# BackBoard.net
KiCad netlist of a schematic drawn in Altium Designer
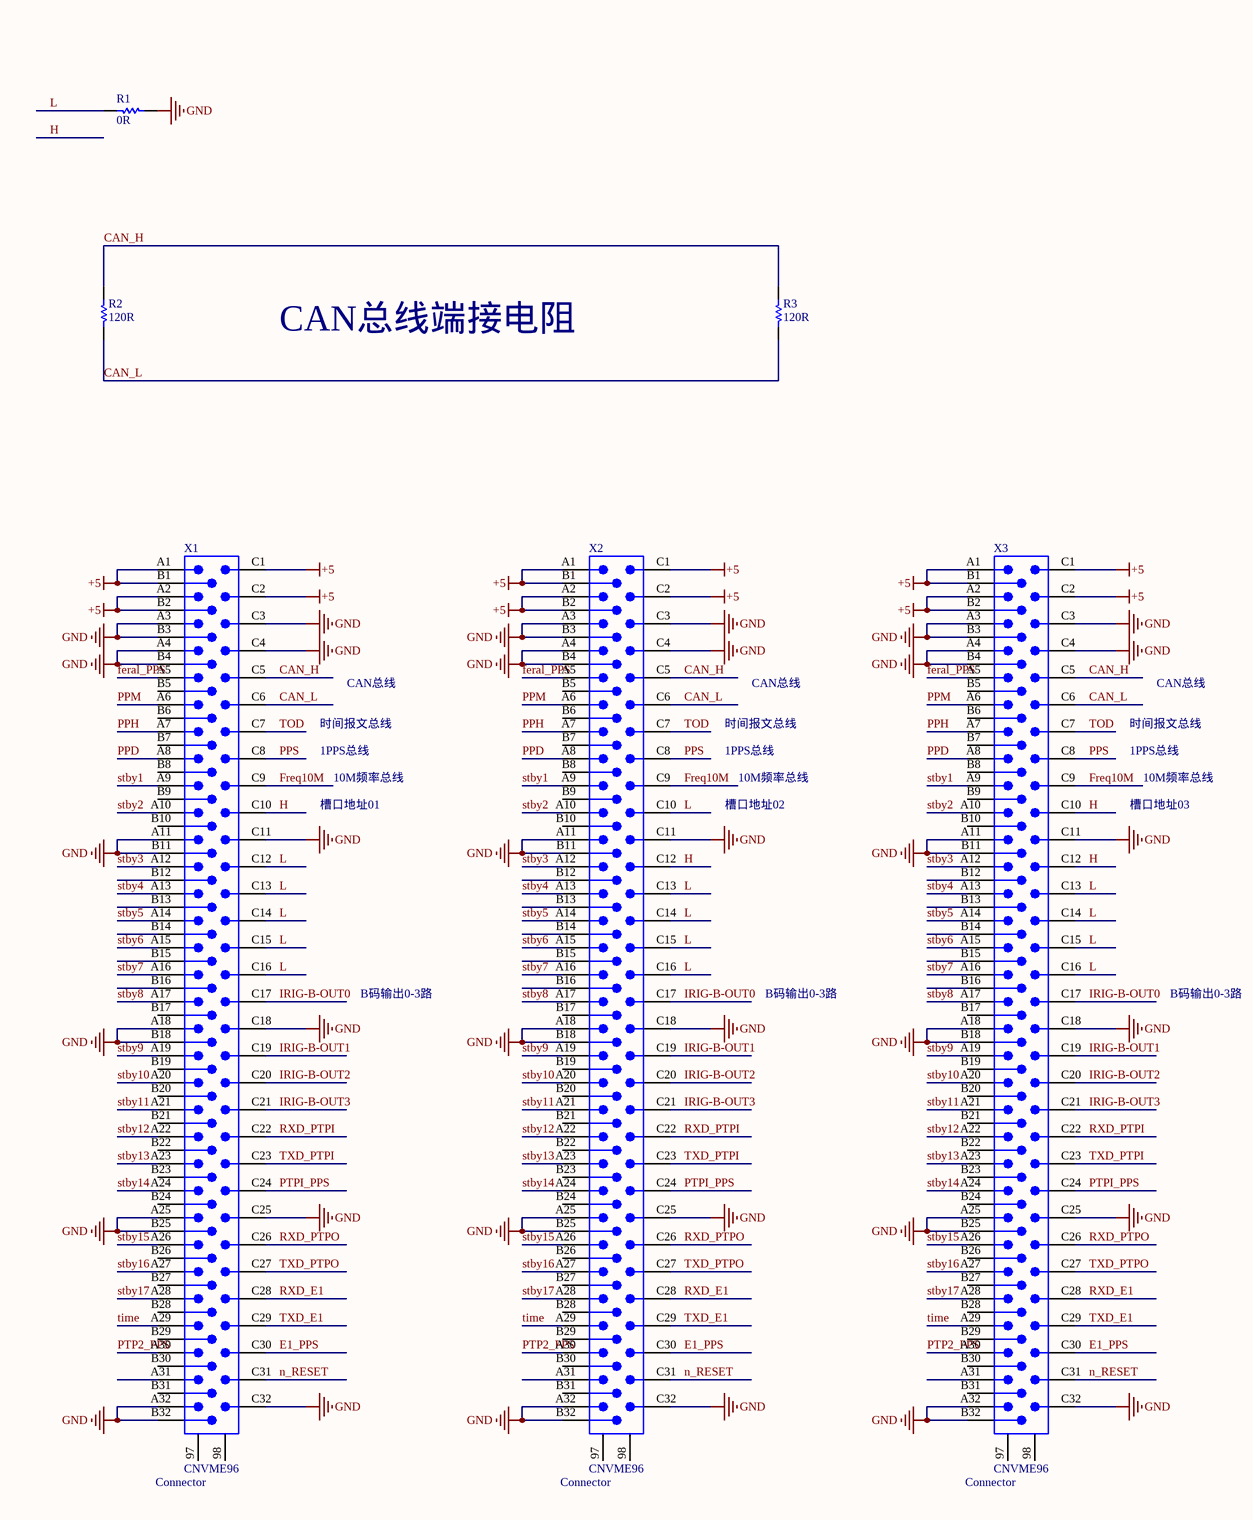
[diagram p0: BackBoard.SchDoc, top left]
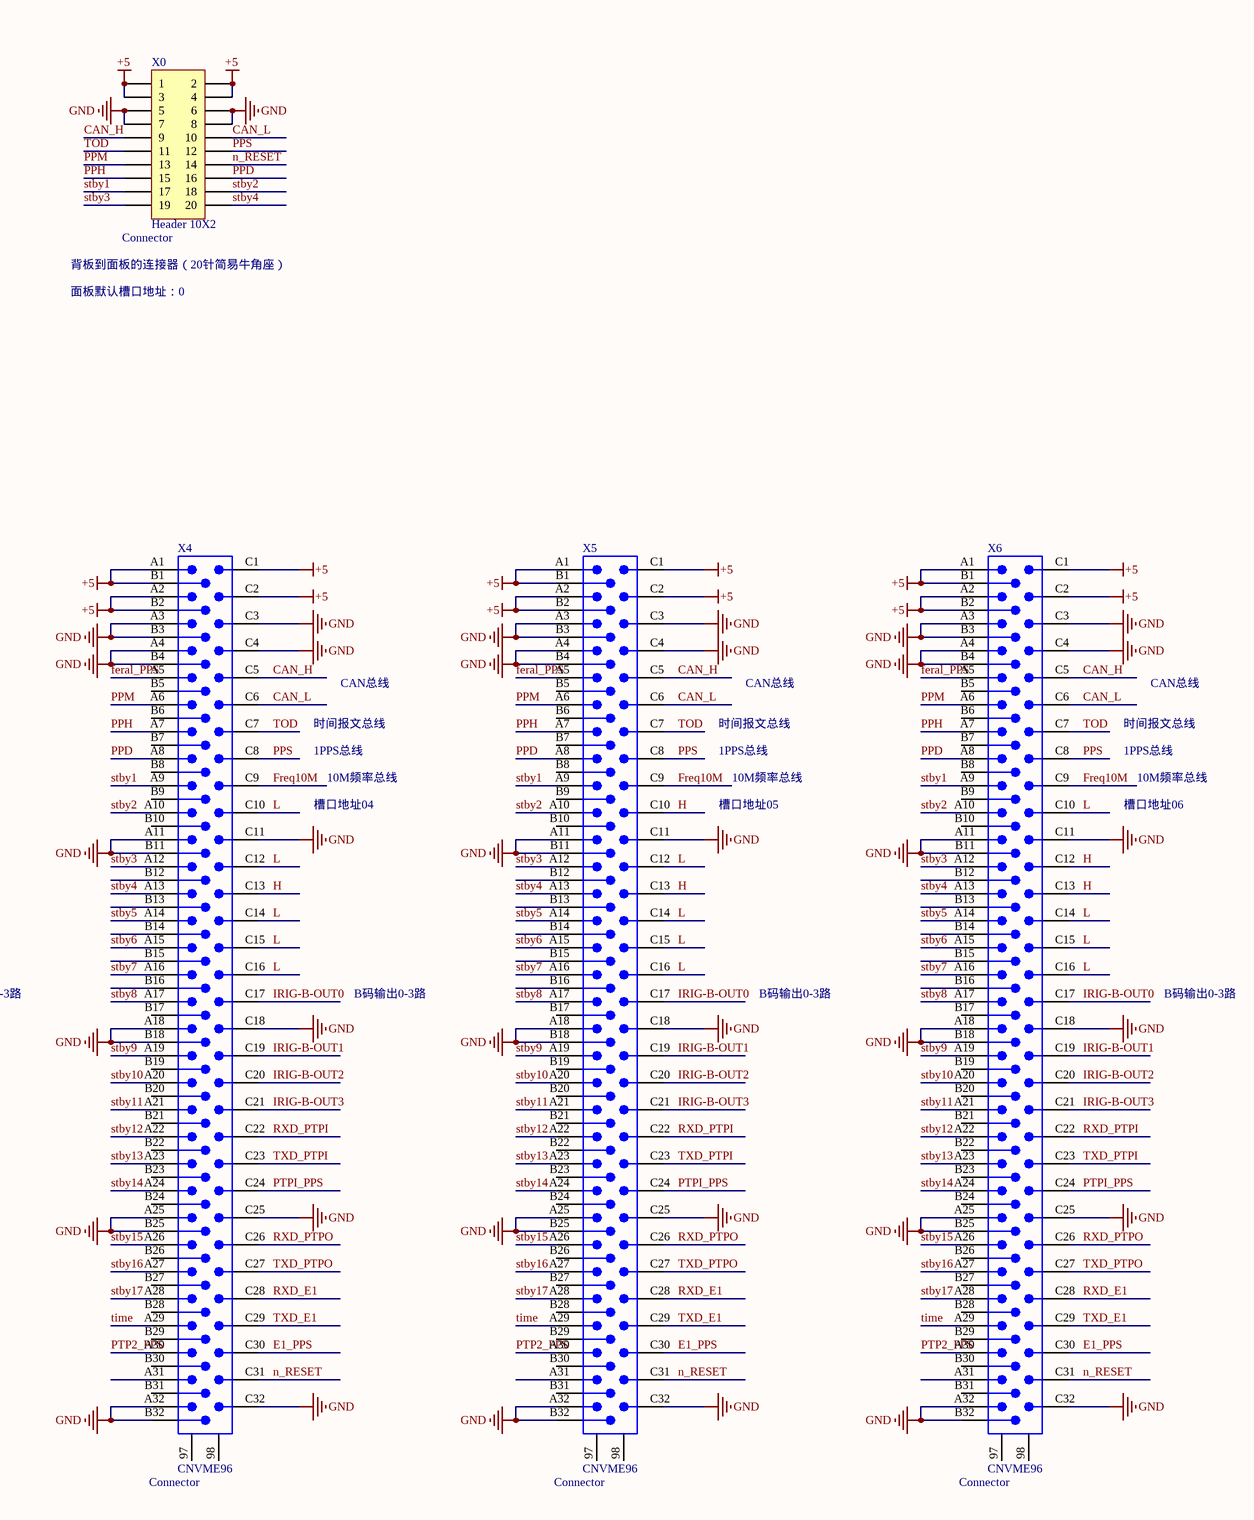
[diagram p1: BackBoard.SchDoc, top right]
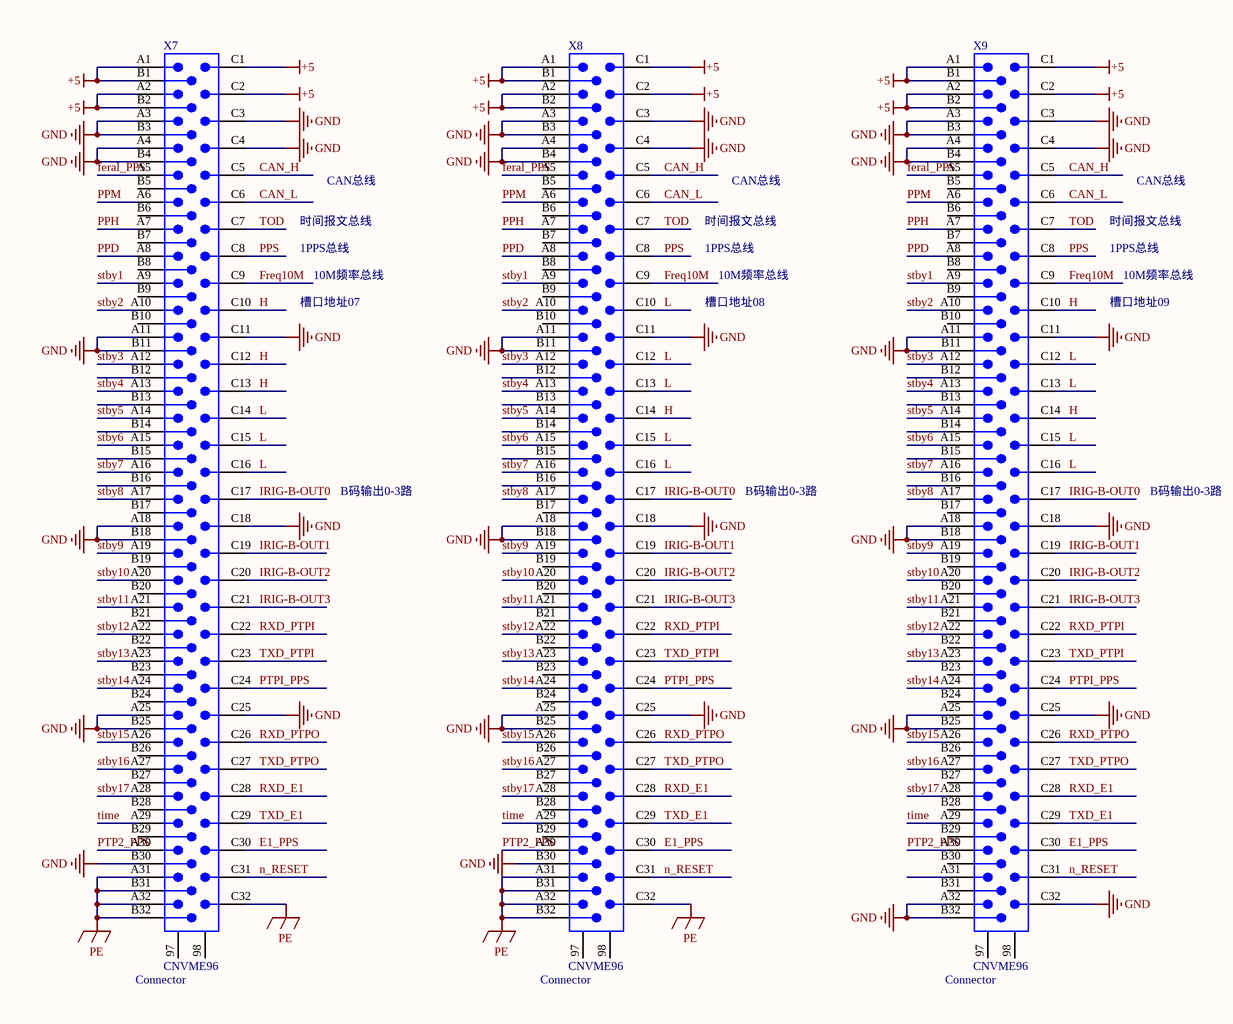
[diagram p2: BackBoard.SchDoc, bottom left]
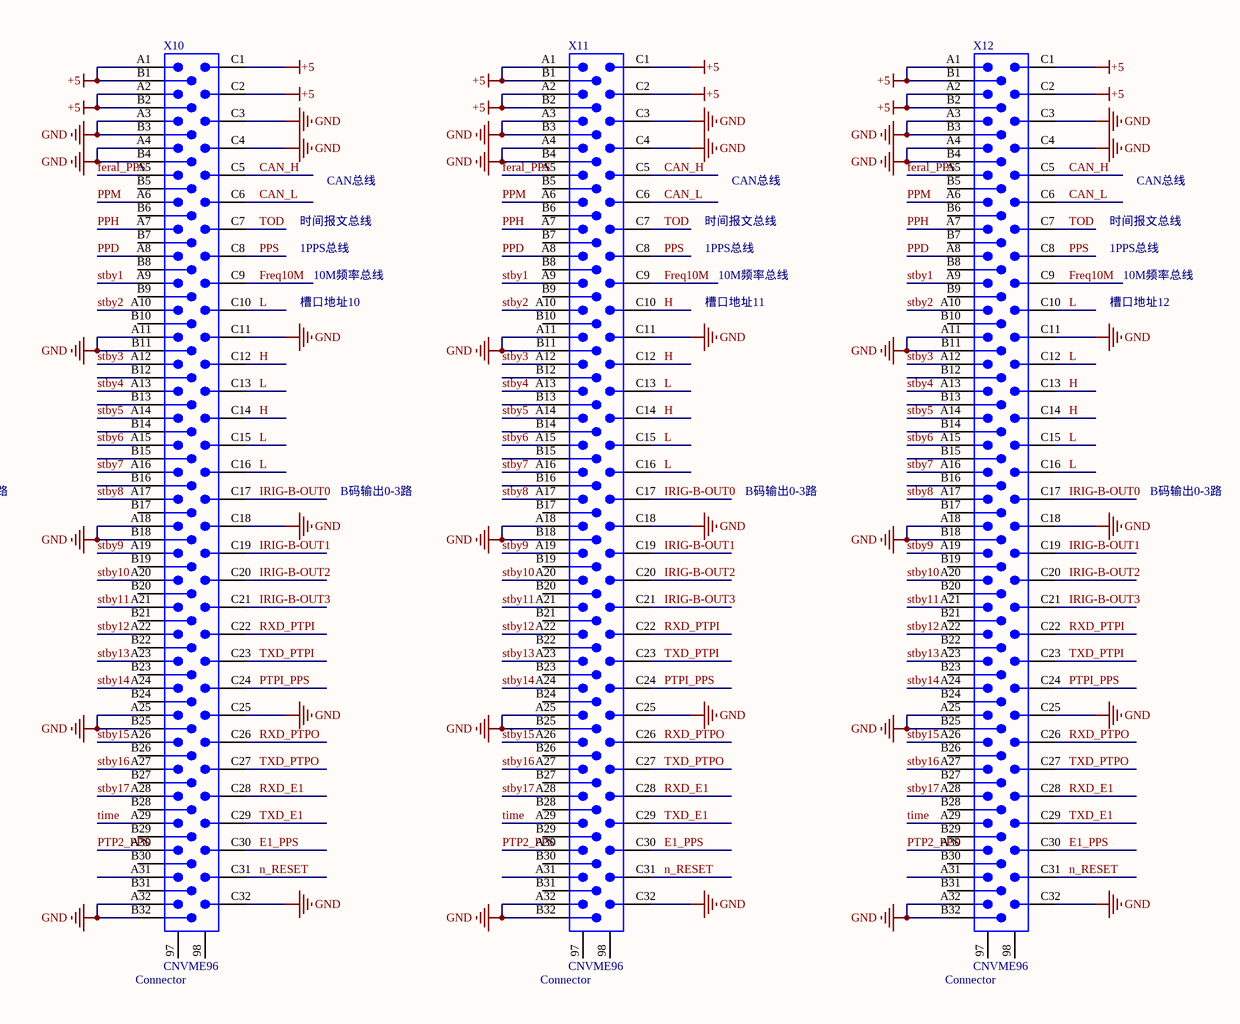
[diagram p3: BackBoard.SchDoc, bottom right]

(export (version "E")
  (design (tool "Eeschema 10.0.6"))
  (components
    (comp (ref "R1")
      (value "0R")
      (footprint "0603_XF")
      (description "Resistor")
      (fields (field (name "Comment") "Res1") (field (name "PUBLISHER") "Altium Limited"))
      (libsource (lib "Miscellaneous Devices") (part "Res1"))
    )
    (comp (ref "R2")
      (value "120R")
      (footprint "0603_XF")
      (description "Resistor")
      (fields (field (name "Comment") "Res1") (field (name "PUBLISHER") "Altium Limited"))
      (libsource (lib "Miscellaneous Devices") (part "Res1"))
    )
    (comp (ref "R3")
      (value "120R")
      (footprint "0603_XF")
      (description "Resistor")
      (fields (field (name "Comment") "Res1") (field (name "PUBLISHER") "Altium Limited"))
      (libsource (lib "Miscellaneous Devices") (part "Res1"))
    )
    (comp (ref "X0")
      (value "Header 10X2")
      (footprint "HDR2X10")
      (description "Header, 10-Pin, Dual row")
      (fields (field (name "SYSTEM") "Connector") (field (name "PUBLISHER") "Altium Limited"))
      (libsource (lib "Miscellaneous Connectors") (part "Header 10X2"))
    )
    (comp (ref "X1")
      (value "CNVME96")
      (footprint "CONNECT_96_Female")
      (description "96-Pin Connector (3x32 2.54mm grid)")
      (fields (field (name "SYSTEM") "Connector"))
      (libsource (lib "BTS4000") (part "CNVME96"))
    )
    (comp (ref "X2")
      (value "CNVME96")
      (footprint "CONNECT_96_Female")
      (description "96-Pin Connector (3x32 2.54mm grid)")
      (fields (field (name "SYSTEM") "Connector"))
      (libsource (lib "BTS4000") (part "CNVME96"))
    )
    (comp (ref "X3")
      (value "CNVME96")
      (footprint "CONNECT_96_Female")
      (description "96-Pin Connector (3x32 2.54mm grid)")
      (fields (field (name "SYSTEM") "Connector"))
      (libsource (lib "BTS4000") (part "CNVME96"))
    )
    (comp (ref "X4")
      (value "CNVME96")
      (footprint "CONNECT_96_Female")
      (description "96-Pin Connector (3x32 2.54mm grid)")
      (fields (field (name "SYSTEM") "Connector"))
      (libsource (lib "BTS4000") (part "CNVME96"))
    )
    (comp (ref "X5")
      (value "CNVME96")
      (footprint "CONNECT_96_Female")
      (description "96-Pin Connector (3x32 2.54mm grid)")
      (fields (field (name "SYSTEM") "Connector"))
      (libsource (lib "BTS4000") (part "CNVME96"))
    )
    (comp (ref "X6")
      (value "CNVME96")
      (footprint "CONNECT_96_Female")
      (description "96-Pin Connector (3x32 2.54mm grid)")
      (fields (field (name "SYSTEM") "Connector"))
      (libsource (lib "BTS4000") (part "CNVME96"))
    )
    (comp (ref "X7")
      (value "CNVME96")
      (footprint "CONNECT_96_Female")
      (description "96-Pin Connector (3x32 2.54mm grid)")
      (fields (field (name "SYSTEM") "Connector"))
      (libsource (lib "BTS4000") (part "CNVME96"))
    )
    (comp (ref "X8")
      (value "CNVME96")
      (footprint "CONNECT_96_Female")
      (description "96-Pin Connector (3x32 2.54mm grid)")
      (fields (field (name "SYSTEM") "Connector"))
      (libsource (lib "BTS4000") (part "CNVME96"))
    )
    (comp (ref "X9")
      (value "CNVME96")
      (footprint "CONNECT_96_Female")
      (description "96-Pin Connector (3x32 2.54mm grid)")
      (fields (field (name "SYSTEM") "Connector"))
      (libsource (lib "BTS4000") (part "CNVME96"))
    )
    (comp (ref "X10")
      (value "CNVME96")
      (footprint "CONNECT_96_Female")
      (description "96-Pin Connector (3x32 2.54mm grid)")
      (fields (field (name "SYSTEM") "Connector"))
      (libsource (lib "BTS4000") (part "CNVME96"))
    )
    (comp (ref "X11")
      (value "CNVME96")
      (footprint "CONNECT_96_Female")
      (description "96-Pin Connector (3x32 2.54mm grid)")
      (fields (field (name "SYSTEM") "Connector"))
      (libsource (lib "BTS4000") (part "CNVME96"))
    )
    (comp (ref "X12")
      (value "CNVME96")
      (footprint "CONNECT_96_Female")
      (description "96-Pin Connector (3x32 2.54mm grid)")
      (fields (field (name "SYSTEM") "Connector"))
      (libsource (lib "BTS4000") (part "CNVME96"))
    )
  )
  (nets
    (net (code "1") (name "+5") (class "Default")
      (node (ref "X0") (pin "1") (pinfunction "1_1") (pintype "passive"))
      (node (ref "X0") (pin "2") (pinfunction "2_2") (pintype "passive"))
      (node (ref "X0") (pin "3") (pinfunction "3_3") (pintype "passive"))
      (node (ref "X0") (pin "4") (pinfunction "4_4") (pintype "passive"))
      (node (ref "X1") (pin "A1") (pinfunction "A1_A1") (pintype "passive"))
      (node (ref "X1") (pin "A2") (pinfunction "A2_A2") (pintype "passive"))
      (node (ref "X1") (pin "B1") (pinfunction "B1_B1") (pintype "passive"))
      (node (ref "X1") (pin "B2") (pinfunction "B2_B2") (pintype "passive"))
      (node (ref "X1") (pin "C1") (pinfunction "C1_C1") (pintype "passive"))
      (node (ref "X1") (pin "C2") (pinfunction "C2_C2") (pintype "passive"))
      (node (ref "X10") (pin "A1") (pinfunction "A1_A1") (pintype "passive"))
      (node (ref "X10") (pin "A2") (pinfunction "A2_A2") (pintype "passive"))
      (node (ref "X10") (pin "B1") (pinfunction "B1_B1") (pintype "passive"))
      (node (ref "X10") (pin "B2") (pinfunction "B2_B2") (pintype "passive"))
      (node (ref "X10") (pin "C1") (pinfunction "C1_C1") (pintype "passive"))
      (node (ref "X10") (pin "C2") (pinfunction "C2_C2") (pintype "passive"))
      (node (ref "X11") (pin "A1") (pinfunction "A1_A1") (pintype "passive"))
      (node (ref "X11") (pin "A2") (pinfunction "A2_A2") (pintype "passive"))
      (node (ref "X11") (pin "B1") (pinfunction "B1_B1") (pintype "passive"))
      (node (ref "X11") (pin "B2") (pinfunction "B2_B2") (pintype "passive"))
      (node (ref "X11") (pin "C1") (pinfunction "C1_C1") (pintype "passive"))
      (node (ref "X11") (pin "C2") (pinfunction "C2_C2") (pintype "passive"))
      (node (ref "X12") (pin "A1") (pinfunction "A1_A1") (pintype "passive"))
      (node (ref "X12") (pin "A2") (pinfunction "A2_A2") (pintype "passive"))
      (node (ref "X12") (pin "B1") (pinfunction "B1_B1") (pintype "passive"))
      (node (ref "X12") (pin "B2") (pinfunction "B2_B2") (pintype "passive"))
      (node (ref "X12") (pin "C1") (pinfunction "C1_C1") (pintype "passive"))
      (node (ref "X12") (pin "C2") (pinfunction "C2_C2") (pintype "passive"))
      (node (ref "X2") (pin "A1") (pinfunction "A1_A1") (pintype "passive"))
      (node (ref "X2") (pin "A2") (pinfunction "A2_A2") (pintype "passive"))
      (node (ref "X2") (pin "B1") (pinfunction "B1_B1") (pintype "passive"))
      (node (ref "X2") (pin "B2") (pinfunction "B2_B2") (pintype "passive"))
      (node (ref "X2") (pin "C1") (pinfunction "C1_C1") (pintype "passive"))
      (node (ref "X2") (pin "C2") (pinfunction "C2_C2") (pintype "passive"))
      (node (ref "X3") (pin "A1") (pinfunction "A1_A1") (pintype "passive"))
      (node (ref "X3") (pin "A2") (pinfunction "A2_A2") (pintype "passive"))
      (node (ref "X3") (pin "B1") (pinfunction "B1_B1") (pintype "passive"))
      (node (ref "X3") (pin "B2") (pinfunction "B2_B2") (pintype "passive"))
      (node (ref "X3") (pin "C1") (pinfunction "C1_C1") (pintype "passive"))
      (node (ref "X3") (pin "C2") (pinfunction "C2_C2") (pintype "passive"))
      (node (ref "X4") (pin "A1") (pinfunction "A1_A1") (pintype "passive"))
      (node (ref "X4") (pin "A2") (pinfunction "A2_A2") (pintype "passive"))
      (node (ref "X4") (pin "B1") (pinfunction "B1_B1") (pintype "passive"))
      (node (ref "X4") (pin "B2") (pinfunction "B2_B2") (pintype "passive"))
      (node (ref "X4") (pin "C1") (pinfunction "C1_C1") (pintype "passive"))
      (node (ref "X4") (pin "C2") (pinfunction "C2_C2") (pintype "passive"))
      (node (ref "X5") (pin "A1") (pinfunction "A1_A1") (pintype "passive"))
      (node (ref "X5") (pin "A2") (pinfunction "A2_A2") (pintype "passive"))
      (node (ref "X5") (pin "B1") (pinfunction "B1_B1") (pintype "passive"))
      (node (ref "X5") (pin "B2") (pinfunction "B2_B2") (pintype "passive"))
      (node (ref "X5") (pin "C1") (pinfunction "C1_C1") (pintype "passive"))
      (node (ref "X5") (pin "C2") (pinfunction "C2_C2") (pintype "passive"))
      (node (ref "X6") (pin "A1") (pinfunction "A1_A1") (pintype "passive"))
      (node (ref "X6") (pin "A2") (pinfunction "A2_A2") (pintype "passive"))
      (node (ref "X6") (pin "B1") (pinfunction "B1_B1") (pintype "passive"))
      (node (ref "X6") (pin "B2") (pinfunction "B2_B2") (pintype "passive"))
      (node (ref "X6") (pin "C1") (pinfunction "C1_C1") (pintype "passive"))
      (node (ref "X6") (pin "C2") (pinfunction "C2_C2") (pintype "passive"))
      (node (ref "X7") (pin "A1") (pinfunction "A1_A1") (pintype "passive"))
      (node (ref "X7") (pin "A2") (pinfunction "A2_A2") (pintype "passive"))
      (node (ref "X7") (pin "B1") (pinfunction "B1_B1") (pintype "passive"))
      (node (ref "X7") (pin "B2") (pinfunction "B2_B2") (pintype "passive"))
      (node (ref "X7") (pin "C1") (pinfunction "C1_C1") (pintype "passive"))
      (node (ref "X7") (pin "C2") (pinfunction "C2_C2") (pintype "passive"))
      (node (ref "X8") (pin "A1") (pinfunction "A1_A1") (pintype "passive"))
      (node (ref "X8") (pin "A2") (pinfunction "A2_A2") (pintype "passive"))
      (node (ref "X8") (pin "B1") (pinfunction "B1_B1") (pintype "passive"))
      (node (ref "X8") (pin "B2") (pinfunction "B2_B2") (pintype "passive"))
      (node (ref "X8") (pin "C1") (pinfunction "C1_C1") (pintype "passive"))
      (node (ref "X8") (pin "C2") (pinfunction "C2_C2") (pintype "passive"))
      (node (ref "X9") (pin "A1") (pinfunction "A1_A1") (pintype "passive"))
      (node (ref "X9") (pin "A2") (pinfunction "A2_A2") (pintype "passive"))
      (node (ref "X9") (pin "B1") (pinfunction "B1_B1") (pintype "passive"))
      (node (ref "X9") (pin "B2") (pinfunction "B2_B2") (pintype "passive"))
      (node (ref "X9") (pin "C1") (pinfunction "C1_C1") (pintype "passive"))
      (node (ref "X9") (pin "C2") (pinfunction "C2_C2") (pintype "passive"))
    )
    (net (code "2") (name "/CAN_H") (class "Default")
      (node (ref "R2") (pin "1") (pinfunction "1_1") (pintype "passive"))
      (node (ref "R3") (pin "2") (pinfunction "2_2") (pintype "passive"))
      (node (ref "X0") (pin "9") (pinfunction "9_9") (pintype "passive"))
      (node (ref "X1") (pin "C5") (pinfunction "C5_C5") (pintype "passive"))
      (node (ref "X10") (pin "C5") (pinfunction "C5_C5") (pintype "passive"))
      (node (ref "X11") (pin "C5") (pinfunction "C5_C5") (pintype "passive"))
      (node (ref "X12") (pin "C5") (pinfunction "C5_C5") (pintype "passive"))
      (node (ref "X2") (pin "C5") (pinfunction "C5_C5") (pintype "passive"))
      (node (ref "X3") (pin "C5") (pinfunction "C5_C5") (pintype "passive"))
      (node (ref "X4") (pin "C5") (pinfunction "C5_C5") (pintype "passive"))
      (node (ref "X5") (pin "C5") (pinfunction "C5_C5") (pintype "passive"))
      (node (ref "X6") (pin "C5") (pinfunction "C5_C5") (pintype "passive"))
      (node (ref "X7") (pin "C5") (pinfunction "C5_C5") (pintype "passive"))
      (node (ref "X8") (pin "C5") (pinfunction "C5_C5") (pintype "passive"))
      (node (ref "X9") (pin "C5") (pinfunction "C5_C5") (pintype "passive"))
    )
    (net (code "3") (name "/CAN_L") (class "Default")
      (node (ref "R2") (pin "2") (pinfunction "2_2") (pintype "passive"))
      (node (ref "R3") (pin "1") (pinfunction "1_1") (pintype "passive"))
      (node (ref "X0") (pin "10") (pinfunction "10_10") (pintype "passive"))
      (node (ref "X1") (pin "C6") (pinfunction "C6_C6") (pintype "passive"))
      (node (ref "X10") (pin "C6") (pinfunction "C6_C6") (pintype "passive"))
      (node (ref "X11") (pin "C6") (pinfunction "C6_C6") (pintype "passive"))
      (node (ref "X12") (pin "C6") (pinfunction "C6_C6") (pintype "passive"))
      (node (ref "X2") (pin "C6") (pinfunction "C6_C6") (pintype "passive"))
      (node (ref "X3") (pin "C6") (pinfunction "C6_C6") (pintype "passive"))
      (node (ref "X4") (pin "C6") (pinfunction "C6_C6") (pintype "passive"))
      (node (ref "X5") (pin "C6") (pinfunction "C6_C6") (pintype "passive"))
      (node (ref "X6") (pin "C6") (pinfunction "C6_C6") (pintype "passive"))
      (node (ref "X7") (pin "C6") (pinfunction "C6_C6") (pintype "passive"))
      (node (ref "X8") (pin "C6") (pinfunction "C6_C6") (pintype "passive"))
      (node (ref "X9") (pin "C6") (pinfunction "C6_C6") (pintype "passive"))
    )
    (net (code "4") (name "/E1_PPS") (class "Default")
      (node (ref "X1") (pin "C30") (pinfunction "C30_C30") (pintype "passive"))
      (node (ref "X10") (pin "C30") (pinfunction "C30_C30") (pintype "passive"))
      (node (ref "X11") (pin "C30") (pinfunction "C30_C30") (pintype "passive"))
      (node (ref "X12") (pin "C30") (pinfunction "C30_C30") (pintype "passive"))
      (node (ref "X2") (pin "C30") (pinfunction "C30_C30") (pintype "passive"))
      (node (ref "X3") (pin "C30") (pinfunction "C30_C30") (pintype "passive"))
      (node (ref "X4") (pin "C30") (pinfunction "C30_C30") (pintype "passive"))
      (node (ref "X5") (pin "C30") (pinfunction "C30_C30") (pintype "passive"))
      (node (ref "X6") (pin "C30") (pinfunction "C30_C30") (pintype "passive"))
      (node (ref "X7") (pin "C30") (pinfunction "C30_C30") (pintype "passive"))
      (node (ref "X8") (pin "C30") (pinfunction "C30_C30") (pintype "passive"))
      (node (ref "X9") (pin "C30") (pinfunction "C30_C30") (pintype "passive"))
    )
    (net (code "5") (name "/Freq10M") (class "Default")
      (node (ref "X1") (pin "C9") (pinfunction "C9_C9") (pintype "passive"))
      (node (ref "X10") (pin "C9") (pinfunction "C9_C9") (pintype "passive"))
      (node (ref "X11") (pin "C9") (pinfunction "C9_C9") (pintype "passive"))
      (node (ref "X12") (pin "C9") (pinfunction "C9_C9") (pintype "passive"))
      (node (ref "X2") (pin "C9") (pinfunction "C9_C9") (pintype "passive"))
      (node (ref "X3") (pin "C9") (pinfunction "C9_C9") (pintype "passive"))
      (node (ref "X4") (pin "C9") (pinfunction "C9_C9") (pintype "passive"))
      (node (ref "X5") (pin "C9") (pinfunction "C9_C9") (pintype "passive"))
      (node (ref "X6") (pin "C9") (pinfunction "C9_C9") (pintype "passive"))
      (node (ref "X7") (pin "C9") (pinfunction "C9_C9") (pintype "passive"))
      (node (ref "X8") (pin "C9") (pinfunction "C9_C9") (pintype "passive"))
      (node (ref "X9") (pin "C9") (pinfunction "C9_C9") (pintype "passive"))
    )
    (net (code "6") (name "/H") (class "Default")
      (node (ref "X1") (pin "C10") (pinfunction "C10_C10") (pintype "passive"))
      (node (ref "X10") (pin "C12") (pinfunction "C12_C12") (pintype "passive"))
      (node (ref "X10") (pin "C14") (pinfunction "C14_C14") (pintype "passive"))
      (node (ref "X11") (pin "C10") (pinfunction "C10_C10") (pintype "passive"))
      (node (ref "X11") (pin "C12") (pinfunction "C12_C12") (pintype "passive"))
      (node (ref "X11") (pin "C14") (pinfunction "C14_C14") (pintype "passive"))
      (node (ref "X12") (pin "C13") (pinfunction "C13_C13") (pintype "passive"))
      (node (ref "X12") (pin "C14") (pinfunction "C14_C14") (pintype "passive"))
      (node (ref "X2") (pin "C12") (pinfunction "C12_C12") (pintype "passive"))
      (node (ref "X3") (pin "C10") (pinfunction "C10_C10") (pintype "passive"))
      (node (ref "X3") (pin "C12") (pinfunction "C12_C12") (pintype "passive"))
      (node (ref "X4") (pin "C13") (pinfunction "C13_C13") (pintype "passive"))
      (node (ref "X5") (pin "C10") (pinfunction "C10_C10") (pintype "passive"))
      (node (ref "X5") (pin "C13") (pinfunction "C13_C13") (pintype "passive"))
      (node (ref "X6") (pin "C12") (pinfunction "C12_C12") (pintype "passive"))
      (node (ref "X6") (pin "C13") (pinfunction "C13_C13") (pintype "passive"))
      (node (ref "X7") (pin "C10") (pinfunction "C10_C10") (pintype "passive"))
      (node (ref "X7") (pin "C12") (pinfunction "C12_C12") (pintype "passive"))
      (node (ref "X7") (pin "C13") (pinfunction "C13_C13") (pintype "passive"))
      (node (ref "X8") (pin "C14") (pinfunction "C14_C14") (pintype "passive"))
      (node (ref "X9") (pin "C10") (pinfunction "C10_C10") (pintype "passive"))
      (node (ref "X9") (pin "C14") (pinfunction "C14_C14") (pintype "passive"))
    )
    (net (code "7") (name "/IRIG-B-OUT0") (class "Default")
      (node (ref "X1") (pin "C17") (pinfunction "C17_C17") (pintype "passive"))
      (node (ref "X10") (pin "C17") (pinfunction "C17_C17") (pintype "passive"))
      (node (ref "X11") (pin "C17") (pinfunction "C17_C17") (pintype "passive"))
      (node (ref "X12") (pin "C17") (pinfunction "C17_C17") (pintype "passive"))
      (node (ref "X2") (pin "C17") (pinfunction "C17_C17") (pintype "passive"))
      (node (ref "X3") (pin "C17") (pinfunction "C17_C17") (pintype "passive"))
      (node (ref "X4") (pin "C17") (pinfunction "C17_C17") (pintype "passive"))
      (node (ref "X5") (pin "C17") (pinfunction "C17_C17") (pintype "passive"))
      (node (ref "X6") (pin "C17") (pinfunction "C17_C17") (pintype "passive"))
      (node (ref "X7") (pin "C17") (pinfunction "C17_C17") (pintype "passive"))
      (node (ref "X8") (pin "C17") (pinfunction "C17_C17") (pintype "passive"))
      (node (ref "X9") (pin "C17") (pinfunction "C17_C17") (pintype "passive"))
    )
    (net (code "8") (name "/IRIG-B-OUT1") (class "Default")
      (node (ref "X1") (pin "C19") (pinfunction "C19_C19") (pintype "passive"))
      (node (ref "X10") (pin "C19") (pinfunction "C19_C19") (pintype "passive"))
      (node (ref "X11") (pin "C19") (pinfunction "C19_C19") (pintype "passive"))
      (node (ref "X12") (pin "C19") (pinfunction "C19_C19") (pintype "passive"))
      (node (ref "X2") (pin "C19") (pinfunction "C19_C19") (pintype "passive"))
      (node (ref "X3") (pin "C19") (pinfunction "C19_C19") (pintype "passive"))
      (node (ref "X4") (pin "C19") (pinfunction "C19_C19") (pintype "passive"))
      (node (ref "X5") (pin "C19") (pinfunction "C19_C19") (pintype "passive"))
      (node (ref "X6") (pin "C19") (pinfunction "C19_C19") (pintype "passive"))
      (node (ref "X7") (pin "C19") (pinfunction "C19_C19") (pintype "passive"))
      (node (ref "X8") (pin "C19") (pinfunction "C19_C19") (pintype "passive"))
      (node (ref "X9") (pin "C19") (pinfunction "C19_C19") (pintype "passive"))
    )
    (net (code "9") (name "/IRIG-B-OUT2") (class "Default")
      (node (ref "X1") (pin "C20") (pinfunction "C20_C20") (pintype "passive"))
      (node (ref "X10") (pin "C20") (pinfunction "C20_C20") (pintype "passive"))
      (node (ref "X11") (pin "C20") (pinfunction "C20_C20") (pintype "passive"))
      (node (ref "X12") (pin "C20") (pinfunction "C20_C20") (pintype "passive"))
      (node (ref "X2") (pin "C20") (pinfunction "C20_C20") (pintype "passive"))
      (node (ref "X3") (pin "C20") (pinfunction "C20_C20") (pintype "passive"))
      (node (ref "X4") (pin "C20") (pinfunction "C20_C20") (pintype "passive"))
      (node (ref "X5") (pin "C20") (pinfunction "C20_C20") (pintype "passive"))
      (node (ref "X6") (pin "C20") (pinfunction "C20_C20") (pintype "passive"))
      (node (ref "X7") (pin "C20") (pinfunction "C20_C20") (pintype "passive"))
      (node (ref "X8") (pin "C20") (pinfunction "C20_C20") (pintype "passive"))
      (node (ref "X9") (pin "C20") (pinfunction "C20_C20") (pintype "passive"))
    )
    (net (code "10") (name "/IRIG-B-OUT3") (class "Default")
      (node (ref "X1") (pin "C21") (pinfunction "C21_C21") (pintype "passive"))
      (node (ref "X10") (pin "C21") (pinfunction "C21_C21") (pintype "passive"))
      (node (ref "X11") (pin "C21") (pinfunction "C21_C21") (pintype "passive"))
      (node (ref "X12") (pin "C21") (pinfunction "C21_C21") (pintype "passive"))
      (node (ref "X2") (pin "C21") (pinfunction "C21_C21") (pintype "passive"))
      (node (ref "X3") (pin "C21") (pinfunction "C21_C21") (pintype "passive"))
      (node (ref "X4") (pin "C21") (pinfunction "C21_C21") (pintype "passive"))
      (node (ref "X5") (pin "C21") (pinfunction "C21_C21") (pintype "passive"))
      (node (ref "X6") (pin "C21") (pinfunction "C21_C21") (pintype "passive"))
      (node (ref "X7") (pin "C21") (pinfunction "C21_C21") (pintype "passive"))
      (node (ref "X8") (pin "C21") (pinfunction "C21_C21") (pintype "passive"))
      (node (ref "X9") (pin "C21") (pinfunction "C21_C21") (pintype "passive"))
    )
    (net (code "11") (name "/L") (class "Default")
      (node (ref "R1") (pin "1") (pinfunction "1_1") (pintype "passive"))
      (node (ref "X1") (pin "C12") (pinfunction "C12_C12") (pintype "passive"))
      (node (ref "X1") (pin "C13") (pinfunction "C13_C13") (pintype "passive"))
      (node (ref "X1") (pin "C14") (pinfunction "C14_C14") (pintype "passive"))
      (node (ref "X1") (pin "C15") (pinfunction "C15_C15") (pintype "passive"))
      (node (ref "X1") (pin "C16") (pinfunction "C16_C16") (pintype "passive"))
      (node (ref "X10") (pin "C10") (pinfunction "C10_C10") (pintype "passive"))
      (node (ref "X10") (pin "C13") (pinfunction "C13_C13") (pintype "passive"))
      (node (ref "X10") (pin "C15") (pinfunction "C15_C15") (pintype "passive"))
      (node (ref "X10") (pin "C16") (pinfunction "C16_C16") (pintype "passive"))
      (node (ref "X11") (pin "C13") (pinfunction "C13_C13") (pintype "passive"))
      (node (ref "X11") (pin "C15") (pinfunction "C15_C15") (pintype "passive"))
      (node (ref "X11") (pin "C16") (pinfunction "C16_C16") (pintype "passive"))
      (node (ref "X12") (pin "C10") (pinfunction "C10_C10") (pintype "passive"))
      (node (ref "X12") (pin "C12") (pinfunction "C12_C12") (pintype "passive"))
      (node (ref "X12") (pin "C15") (pinfunction "C15_C15") (pintype "passive"))
      (node (ref "X12") (pin "C16") (pinfunction "C16_C16") (pintype "passive"))
      (node (ref "X2") (pin "C10") (pinfunction "C10_C10") (pintype "passive"))
      (node (ref "X2") (pin "C13") (pinfunction "C13_C13") (pintype "passive"))
      (node (ref "X2") (pin "C14") (pinfunction "C14_C14") (pintype "passive"))
      (node (ref "X2") (pin "C15") (pinfunction "C15_C15") (pintype "passive"))
      (node (ref "X2") (pin "C16") (pinfunction "C16_C16") (pintype "passive"))
      (node (ref "X3") (pin "C13") (pinfunction "C13_C13") (pintype "passive"))
      (node (ref "X3") (pin "C14") (pinfunction "C14_C14") (pintype "passive"))
      (node (ref "X3") (pin "C15") (pinfunction "C15_C15") (pintype "passive"))
      (node (ref "X3") (pin "C16") (pinfunction "C16_C16") (pintype "passive"))
      (node (ref "X4") (pin "C10") (pinfunction "C10_C10") (pintype "passive"))
      (node (ref "X4") (pin "C12") (pinfunction "C12_C12") (pintype "passive"))
      (node (ref "X4") (pin "C14") (pinfunction "C14_C14") (pintype "passive"))
      (node (ref "X4") (pin "C15") (pinfunction "C15_C15") (pintype "passive"))
      (node (ref "X4") (pin "C16") (pinfunction "C16_C16") (pintype "passive"))
      (node (ref "X5") (pin "C12") (pinfunction "C12_C12") (pintype "passive"))
      (node (ref "X5") (pin "C14") (pinfunction "C14_C14") (pintype "passive"))
      (node (ref "X5") (pin "C15") (pinfunction "C15_C15") (pintype "passive"))
      (node (ref "X5") (pin "C16") (pinfunction "C16_C16") (pintype "passive"))
      (node (ref "X6") (pin "C10") (pinfunction "C10_C10") (pintype "passive"))
      (node (ref "X6") (pin "C14") (pinfunction "C14_C14") (pintype "passive"))
      (node (ref "X6") (pin "C15") (pinfunction "C15_C15") (pintype "passive"))
      (node (ref "X6") (pin "C16") (pinfunction "C16_C16") (pintype "passive"))
      (node (ref "X7") (pin "C14") (pinfunction "C14_C14") (pintype "passive"))
      (node (ref "X7") (pin "C15") (pinfunction "C15_C15") (pintype "passive"))
      (node (ref "X7") (pin "C16") (pinfunction "C16_C16") (pintype "passive"))
      (node (ref "X8") (pin "C10") (pinfunction "C10_C10") (pintype "passive"))
      (node (ref "X8") (pin "C12") (pinfunction "C12_C12") (pintype "passive"))
      (node (ref "X8") (pin "C13") (pinfunction "C13_C13") (pintype "passive"))
      (node (ref "X8") (pin "C15") (pinfunction "C15_C15") (pintype "passive"))
      (node (ref "X8") (pin "C16") (pinfunction "C16_C16") (pintype "passive"))
      (node (ref "X9") (pin "C12") (pinfunction "C12_C12") (pintype "passive"))
      (node (ref "X9") (pin "C13") (pinfunction "C13_C13") (pintype "passive"))
      (node (ref "X9") (pin "C15") (pinfunction "C15_C15") (pintype "passive"))
      (node (ref "X9") (pin "C16") (pinfunction "C16_C16") (pintype "passive"))
    )
    (net (code "12") (name "/PPD") (class "Default")
      (node (ref "X0") (pin "16") (pinfunction "16_16") (pintype "passive"))
      (node (ref "X1") (pin "A8") (pinfunction "A8_A8") (pintype "passive"))
      (node (ref "X10") (pin "A8") (pinfunction "A8_A8") (pintype "passive"))
      (node (ref "X11") (pin "A8") (pinfunction "A8_A8") (pintype "passive"))
      (node (ref "X12") (pin "A8") (pinfunction "A8_A8") (pintype "passive"))
      (node (ref "X2") (pin "A8") (pinfunction "A8_A8") (pintype "passive"))
      (node (ref "X3") (pin "A8") (pinfunction "A8_A8") (pintype "passive"))
      (node (ref "X4") (pin "A8") (pinfunction "A8_A8") (pintype "passive"))
      (node (ref "X5") (pin "A8") (pinfunction "A8_A8") (pintype "passive"))
      (node (ref "X6") (pin "A8") (pinfunction "A8_A8") (pintype "passive"))
      (node (ref "X7") (pin "A8") (pinfunction "A8_A8") (pintype "passive"))
      (node (ref "X8") (pin "A8") (pinfunction "A8_A8") (pintype "passive"))
      (node (ref "X9") (pin "A8") (pinfunction "A8_A8") (pintype "passive"))
    )
    (net (code "13") (name "/PPH") (class "Default")
      (node (ref "X0") (pin "15") (pinfunction "15_15") (pintype "passive"))
      (node (ref "X1") (pin "A7") (pinfunction "A7_A7") (pintype "passive"))
      (node (ref "X10") (pin "A7") (pinfunction "A7_A7") (pintype "passive"))
      (node (ref "X11") (pin "A7") (pinfunction "A7_A7") (pintype "passive"))
      (node (ref "X12") (pin "A7") (pinfunction "A7_A7") (pintype "passive"))
      (node (ref "X2") (pin "A7") (pinfunction "A7_A7") (pintype "passive"))
      (node (ref "X3") (pin "A7") (pinfunction "A7_A7") (pintype "passive"))
      (node (ref "X4") (pin "A7") (pinfunction "A7_A7") (pintype "passive"))
      (node (ref "X5") (pin "A7") (pinfunction "A7_A7") (pintype "passive"))
      (node (ref "X6") (pin "A7") (pinfunction "A7_A7") (pintype "passive"))
      (node (ref "X7") (pin "A7") (pinfunction "A7_A7") (pintype "passive"))
      (node (ref "X8") (pin "A7") (pinfunction "A7_A7") (pintype "passive"))
      (node (ref "X9") (pin "A7") (pinfunction "A7_A7") (pintype "passive"))
    )
    (net (code "14") (name "/PPM") (class "Default")
      (node (ref "X0") (pin "13") (pinfunction "13_13") (pintype "passive"))
      (node (ref "X1") (pin "A6") (pinfunction "A6_A6") (pintype "passive"))
      (node (ref "X10") (pin "A6") (pinfunction "A6_A6") (pintype "passive"))
      (node (ref "X11") (pin "A6") (pinfunction "A6_A6") (pintype "passive"))
      (node (ref "X12") (pin "A6") (pinfunction "A6_A6") (pintype "passive"))
      (node (ref "X2") (pin "A6") (pinfunction "A6_A6") (pintype "passive"))
      (node (ref "X3") (pin "A6") (pinfunction "A6_A6") (pintype "passive"))
      (node (ref "X4") (pin "A6") (pinfunction "A6_A6") (pintype "passive"))
      (node (ref "X5") (pin "A6") (pinfunction "A6_A6") (pintype "passive"))
      (node (ref "X6") (pin "A6") (pinfunction "A6_A6") (pintype "passive"))
      (node (ref "X7") (pin "A6") (pinfunction "A6_A6") (pintype "passive"))
      (node (ref "X8") (pin "A6") (pinfunction "A6_A6") (pintype "passive"))
      (node (ref "X9") (pin "A6") (pinfunction "A6_A6") (pintype "passive"))
    )
    (net (code "15") (name "/PPS") (class "Default")
      (node (ref "X0") (pin "12") (pinfunction "12_12") (pintype "passive"))
      (node (ref "X1") (pin "C8") (pinfunction "C8_C8") (pintype "passive"))
      (node (ref "X10") (pin "C8") (pinfunction "C8_C8") (pintype "passive"))
      (node (ref "X11") (pin "C8") (pinfunction "C8_C8") (pintype "passive"))
      (node (ref "X12") (pin "C8") (pinfunction "C8_C8") (pintype "passive"))
      (node (ref "X2") (pin "C8") (pinfunction "C8_C8") (pintype "passive"))
      (node (ref "X3") (pin "C8") (pinfunction "C8_C8") (pintype "passive"))
      (node (ref "X4") (pin "C8") (pinfunction "C8_C8") (pintype "passive"))
      (node (ref "X5") (pin "C8") (pinfunction "C8_C8") (pintype "passive"))
      (node (ref "X6") (pin "C8") (pinfunction "C8_C8") (pintype "passive"))
      (node (ref "X7") (pin "C8") (pinfunction "C8_C8") (pintype "passive"))
      (node (ref "X8") (pin "C8") (pinfunction "C8_C8") (pintype "passive"))
      (node (ref "X9") (pin "C8") (pinfunction "C8_C8") (pintype "passive"))
    )
    (net (code "16") (name "/PTP2_PPS") (class "Default")
      (node (ref "X1") (pin "A30") (pinfunction "A30_A30") (pintype "passive"))
      (node (ref "X10") (pin "A30") (pinfunction "A30_A30") (pintype "passive"))
      (node (ref "X11") (pin "A30") (pinfunction "A30_A30") (pintype "passive"))
      (node (ref "X12") (pin "A30") (pinfunction "A30_A30") (pintype "passive"))
      (node (ref "X2") (pin "A30") (pinfunction "A30_A30") (pintype "passive"))
      (node (ref "X3") (pin "A30") (pinfunction "A30_A30") (pintype "passive"))
      (node (ref "X4") (pin "A30") (pinfunction "A30_A30") (pintype "passive"))
      (node (ref "X5") (pin "A30") (pinfunction "A30_A30") (pintype "passive"))
      (node (ref "X6") (pin "A30") (pinfunction "A30_A30") (pintype "passive"))
      (node (ref "X7") (pin "A30") (pinfunction "A30_A30") (pintype "passive"))
      (node (ref "X8") (pin "A30") (pinfunction "A30_A30") (pintype "passive"))
      (node (ref "X9") (pin "A30") (pinfunction "A30_A30") (pintype "passive"))
    )
    (net (code "17") (name "/PTPI_PPS") (class "Default")
      (node (ref "X1") (pin "C24") (pinfunction "C24_C24") (pintype "passive"))
      (node (ref "X10") (pin "C24") (pinfunction "C24_C24") (pintype "passive"))
      (node (ref "X11") (pin "C24") (pinfunction "C24_C24") (pintype "passive"))
      (node (ref "X12") (pin "C24") (pinfunction "C24_C24") (pintype "passive"))
      (node (ref "X2") (pin "C24") (pinfunction "C24_C24") (pintype "passive"))
      (node (ref "X3") (pin "C24") (pinfunction "C24_C24") (pintype "passive"))
      (node (ref "X4") (pin "C24") (pinfunction "C24_C24") (pintype "passive"))
      (node (ref "X5") (pin "C24") (pinfunction "C24_C24") (pintype "passive"))
      (node (ref "X6") (pin "C24") (pinfunction "C24_C24") (pintype "passive"))
      (node (ref "X7") (pin "C24") (pinfunction "C24_C24") (pintype "passive"))
      (node (ref "X8") (pin "C24") (pinfunction "C24_C24") (pintype "passive"))
      (node (ref "X9") (pin "C24") (pinfunction "C24_C24") (pintype "passive"))
    )
    (net (code "18") (name "/RXD_E1") (class "Default")
      (node (ref "X1") (pin "C28") (pinfunction "C28_C28") (pintype "passive"))
      (node (ref "X10") (pin "C28") (pinfunction "C28_C28") (pintype "passive"))
      (node (ref "X11") (pin "C28") (pinfunction "C28_C28") (pintype "passive"))
      (node (ref "X12") (pin "C28") (pinfunction "C28_C28") (pintype "passive"))
      (node (ref "X2") (pin "C28") (pinfunction "C28_C28") (pintype "passive"))
      (node (ref "X3") (pin "C28") (pinfunction "C28_C28") (pintype "passive"))
      (node (ref "X4") (pin "C28") (pinfunction "C28_C28") (pintype "passive"))
      (node (ref "X5") (pin "C28") (pinfunction "C28_C28") (pintype "passive"))
      (node (ref "X6") (pin "C28") (pinfunction "C28_C28") (pintype "passive"))
      (node (ref "X7") (pin "C28") (pinfunction "C28_C28") (pintype "passive"))
      (node (ref "X8") (pin "C28") (pinfunction "C28_C28") (pintype "passive"))
      (node (ref "X9") (pin "C28") (pinfunction "C28_C28") (pintype "passive"))
    )
    (net (code "19") (name "/RXD_PTPI") (class "Default")
      (node (ref "X1") (pin "C22") (pinfunction "C22_C22") (pintype "passive"))
      (node (ref "X10") (pin "C22") (pinfunction "C22_C22") (pintype "passive"))
      (node (ref "X11") (pin "C22") (pinfunction "C22_C22") (pintype "passive"))
      (node (ref "X12") (pin "C22") (pinfunction "C22_C22") (pintype "passive"))
      (node (ref "X2") (pin "C22") (pinfunction "C22_C22") (pintype "passive"))
      (node (ref "X3") (pin "C22") (pinfunction "C22_C22") (pintype "passive"))
      (node (ref "X4") (pin "C22") (pinfunction "C22_C22") (pintype "passive"))
      (node (ref "X5") (pin "C22") (pinfunction "C22_C22") (pintype "passive"))
      (node (ref "X6") (pin "C22") (pinfunction "C22_C22") (pintype "passive"))
      (node (ref "X7") (pin "C22") (pinfunction "C22_C22") (pintype "passive"))
      (node (ref "X8") (pin "C22") (pinfunction "C22_C22") (pintype "passive"))
      (node (ref "X9") (pin "C22") (pinfunction "C22_C22") (pintype "passive"))
    )
    (net (code "20") (name "/RXD_PTPO") (class "Default")
      (node (ref "X1") (pin "C26") (pinfunction "C26_C26") (pintype "passive"))
      (node (ref "X10") (pin "C26") (pinfunction "C26_C26") (pintype "passive"))
      (node (ref "X11") (pin "C26") (pinfunction "C26_C26") (pintype "passive"))
      (node (ref "X12") (pin "C26") (pinfunction "C26_C26") (pintype "passive"))
      (node (ref "X2") (pin "C26") (pinfunction "C26_C26") (pintype "passive"))
      (node (ref "X3") (pin "C26") (pinfunction "C26_C26") (pintype "passive"))
      (node (ref "X4") (pin "C26") (pinfunction "C26_C26") (pintype "passive"))
      (node (ref "X5") (pin "C26") (pinfunction "C26_C26") (pintype "passive"))
      (node (ref "X6") (pin "C26") (pinfunction "C26_C26") (pintype "passive"))
      (node (ref "X7") (pin "C26") (pinfunction "C26_C26") (pintype "passive"))
      (node (ref "X8") (pin "C26") (pinfunction "C26_C26") (pintype "passive"))
      (node (ref "X9") (pin "C26") (pinfunction "C26_C26") (pintype "passive"))
    )
    (net (code "21") (name "/TOD") (class "Default")
      (node (ref "X0") (pin "11") (pinfunction "11_11") (pintype "passive"))
      (node (ref "X1") (pin "C7") (pinfunction "C7_C7") (pintype "passive"))
      (node (ref "X10") (pin "C7") (pinfunction "C7_C7") (pintype "passive"))
      (node (ref "X11") (pin "C7") (pinfunction "C7_C7") (pintype "passive"))
      (node (ref "X12") (pin "C7") (pinfunction "C7_C7") (pintype "passive"))
      (node (ref "X2") (pin "C7") (pinfunction "C7_C7") (pintype "passive"))
      (node (ref "X3") (pin "C7") (pinfunction "C7_C7") (pintype "passive"))
      (node (ref "X4") (pin "C7") (pinfunction "C7_C7") (pintype "passive"))
      (node (ref "X5") (pin "C7") (pinfunction "C7_C7") (pintype "passive"))
      (node (ref "X6") (pin "C7") (pinfunction "C7_C7") (pintype "passive"))
      (node (ref "X7") (pin "C7") (pinfunction "C7_C7") (pintype "passive"))
      (node (ref "X8") (pin "C7") (pinfunction "C7_C7") (pintype "passive"))
      (node (ref "X9") (pin "C7") (pinfunction "C7_C7") (pintype "passive"))
    )
    (net (code "22") (name "/TXD_E1") (class "Default")
      (node (ref "X1") (pin "C29") (pinfunction "C29_C29") (pintype "passive"))
      (node (ref "X10") (pin "C29") (pinfunction "C29_C29") (pintype "passive"))
      (node (ref "X11") (pin "C29") (pinfunction "C29_C29") (pintype "passive"))
      (node (ref "X12") (pin "C29") (pinfunction "C29_C29") (pintype "passive"))
      (node (ref "X2") (pin "C29") (pinfunction "C29_C29") (pintype "passive"))
      (node (ref "X3") (pin "C29") (pinfunction "C29_C29") (pintype "passive"))
      (node (ref "X4") (pin "C29") (pinfunction "C29_C29") (pintype "passive"))
      (node (ref "X5") (pin "C29") (pinfunction "C29_C29") (pintype "passive"))
      (node (ref "X6") (pin "C29") (pinfunction "C29_C29") (pintype "passive"))
      (node (ref "X7") (pin "C29") (pinfunction "C29_C29") (pintype "passive"))
      (node (ref "X8") (pin "C29") (pinfunction "C29_C29") (pintype "passive"))
      (node (ref "X9") (pin "C29") (pinfunction "C29_C29") (pintype "passive"))
    )
    (net (code "23") (name "/TXD_PTPI") (class "Default")
      (node (ref "X1") (pin "C23") (pinfunction "C23_C23") (pintype "passive"))
      (node (ref "X10") (pin "C23") (pinfunction "C23_C23") (pintype "passive"))
      (node (ref "X11") (pin "C23") (pinfunction "C23_C23") (pintype "passive"))
      (node (ref "X12") (pin "C23") (pinfunction "C23_C23") (pintype "passive"))
      (node (ref "X2") (pin "C23") (pinfunction "C23_C23") (pintype "passive"))
      (node (ref "X3") (pin "C23") (pinfunction "C23_C23") (pintype "passive"))
      (node (ref "X4") (pin "C23") (pinfunction "C23_C23") (pintype "passive"))
      (node (ref "X5") (pin "C23") (pinfunction "C23_C23") (pintype "passive"))
      (node (ref "X6") (pin "C23") (pinfunction "C23_C23") (pintype "passive"))
      (node (ref "X7") (pin "C23") (pinfunction "C23_C23") (pintype "passive"))
      (node (ref "X8") (pin "C23") (pinfunction "C23_C23") (pintype "passive"))
      (node (ref "X9") (pin "C23") (pinfunction "C23_C23") (pintype "passive"))
    )
    (net (code "24") (name "/TXD_PTPO") (class "Default")
      (node (ref "X1") (pin "C27") (pinfunction "C27_C27") (pintype "passive"))
      (node (ref "X10") (pin "C27") (pinfunction "C27_C27") (pintype "passive"))
      (node (ref "X11") (pin "C27") (pinfunction "C27_C27") (pintype "passive"))
      (node (ref "X12") (pin "C27") (pinfunction "C27_C27") (pintype "passive"))
      (node (ref "X2") (pin "C27") (pinfunction "C27_C27") (pintype "passive"))
      (node (ref "X3") (pin "C27") (pinfunction "C27_C27") (pintype "passive"))
      (node (ref "X4") (pin "C27") (pinfunction "C27_C27") (pintype "passive"))
      (node (ref "X5") (pin "C27") (pinfunction "C27_C27") (pintype "passive"))
      (node (ref "X6") (pin "C27") (pinfunction "C27_C27") (pintype "passive"))
      (node (ref "X7") (pin "C27") (pinfunction "C27_C27") (pintype "passive"))
      (node (ref "X8") (pin "C27") (pinfunction "C27_C27") (pintype "passive"))
      (node (ref "X9") (pin "C27") (pinfunction "C27_C27") (pintype "passive"))
    )
    (net (code "25") (name "/feral_PPS") (class "Default")
      (node (ref "X1") (pin "A5") (pinfunction "A5_A5") (pintype "passive"))
      (node (ref "X10") (pin "A5") (pinfunction "A5_A5") (pintype "passive"))
      (node (ref "X11") (pin "A5") (pinfunction "A5_A5") (pintype "passive"))
      (node (ref "X12") (pin "A5") (pinfunction "A5_A5") (pintype "passive"))
      (node (ref "X2") (pin "A5") (pinfunction "A5_A5") (pintype "passive"))
      (node (ref "X3") (pin "A5") (pinfunction "A5_A5") (pintype "passive"))
      (node (ref "X4") (pin "A5") (pinfunction "A5_A5") (pintype "passive"))
      (node (ref "X5") (pin "A5") (pinfunction "A5_A5") (pintype "passive"))
      (node (ref "X6") (pin "A5") (pinfunction "A5_A5") (pintype "passive"))
      (node (ref "X7") (pin "A5") (pinfunction "A5_A5") (pintype "passive"))
      (node (ref "X8") (pin "A5") (pinfunction "A5_A5") (pintype "passive"))
      (node (ref "X9") (pin "A5") (pinfunction "A5_A5") (pintype "passive"))
    )
    (net (code "26") (name "/n_RESET") (class "Default")
      (node (ref "X0") (pin "14") (pinfunction "14_14") (pintype "passive"))
      (node (ref "X1") (pin "C31") (pinfunction "C31_C31") (pintype "passive"))
      (node (ref "X10") (pin "C31") (pinfunction "C31_C31") (pintype "passive"))
      (node (ref "X11") (pin "C31") (pinfunction "C31_C31") (pintype "passive"))
      (node (ref "X12") (pin "C31") (pinfunction "C31_C31") (pintype "passive"))
      (node (ref "X2") (pin "C31") (pinfunction "C31_C31") (pintype "passive"))
      (node (ref "X3") (pin "C31") (pinfunction "C31_C31") (pintype "passive"))
      (node (ref "X4") (pin "C31") (pinfunction "C31_C31") (pintype "passive"))
      (node (ref "X5") (pin "C31") (pinfunction "C31_C31") (pintype "passive"))
      (node (ref "X6") (pin "C31") (pinfunction "C31_C31") (pintype "passive"))
      (node (ref "X7") (pin "C31") (pinfunction "C31_C31") (pintype "passive"))
      (node (ref "X8") (pin "C31") (pinfunction "C31_C31") (pintype "passive"))
      (node (ref "X9") (pin "C31") (pinfunction "C31_C31") (pintype "passive"))
    )
    (net (code "27") (name "/stby1") (class "Default")
      (node (ref "X0") (pin "17") (pinfunction "17_17") (pintype "passive"))
      (node (ref "X1") (pin "A9") (pinfunction "A9_A9") (pintype "passive"))
      (node (ref "X10") (pin "A9") (pinfunction "A9_A9") (pintype "passive"))
      (node (ref "X11") (pin "A9") (pinfunction "A9_A9") (pintype "passive"))
      (node (ref "X12") (pin "A9") (pinfunction "A9_A9") (pintype "passive"))
      (node (ref "X2") (pin "A9") (pinfunction "A9_A9") (pintype "passive"))
      (node (ref "X3") (pin "A9") (pinfunction "A9_A9") (pintype "passive"))
      (node (ref "X4") (pin "A9") (pinfunction "A9_A9") (pintype "passive"))
      (node (ref "X5") (pin "A9") (pinfunction "A9_A9") (pintype "passive"))
      (node (ref "X6") (pin "A9") (pinfunction "A9_A9") (pintype "passive"))
      (node (ref "X7") (pin "A9") (pinfunction "A9_A9") (pintype "passive"))
      (node (ref "X8") (pin "A9") (pinfunction "A9_A9") (pintype "passive"))
      (node (ref "X9") (pin "A9") (pinfunction "A9_A9") (pintype "passive"))
    )
    (net (code "28") (name "/stby2") (class "Default")
      (node (ref "X0") (pin "18") (pinfunction "18_18") (pintype "passive"))
      (node (ref "X1") (pin "A10") (pinfunction "A10_A10") (pintype "passive"))
      (node (ref "X10") (pin "A10") (pinfunction "A10_A10") (pintype "passive"))
      (node (ref "X11") (pin "A10") (pinfunction "A10_A10") (pintype "passive"))
      (node (ref "X12") (pin "A10") (pinfunction "A10_A10") (pintype "passive"))
      (node (ref "X2") (pin "A10") (pinfunction "A10_A10") (pintype "passive"))
      (node (ref "X3") (pin "A10") (pinfunction "A10_A10") (pintype "passive"))
      (node (ref "X4") (pin "A10") (pinfunction "A10_A10") (pintype "passive"))
      (node (ref "X5") (pin "A10") (pinfunction "A10_A10") (pintype "passive"))
      (node (ref "X6") (pin "A10") (pinfunction "A10_A10") (pintype "passive"))
      (node (ref "X7") (pin "A10") (pinfunction "A10_A10") (pintype "passive"))
      (node (ref "X8") (pin "A10") (pinfunction "A10_A10") (pintype "passive"))
      (node (ref "X9") (pin "A10") (pinfunction "A10_A10") (pintype "passive"))
    )
    (net (code "29") (name "/stby3") (class "Default")
      (node (ref "X0") (pin "19") (pinfunction "19_19") (pintype "passive"))
      (node (ref "X1") (pin "A12") (pinfunction "A12_A12") (pintype "passive"))
      (node (ref "X10") (pin "A12") (pinfunction "A12_A12") (pintype "passive"))
      (node (ref "X11") (pin "A12") (pinfunction "A12_A12") (pintype "passive"))
      (node (ref "X12") (pin "A12") (pinfunction "A12_A12") (pintype "passive"))
      (node (ref "X2") (pin "A12") (pinfunction "A12_A12") (pintype "passive"))
      (node (ref "X3") (pin "A12") (pinfunction "A12_A12") (pintype "passive"))
      (node (ref "X4") (pin "A12") (pinfunction "A12_A12") (pintype "passive"))
      (node (ref "X5") (pin "A12") (pinfunction "A12_A12") (pintype "passive"))
      (node (ref "X6") (pin "A12") (pinfunction "A12_A12") (pintype "passive"))
      (node (ref "X7") (pin "A12") (pinfunction "A12_A12") (pintype "passive"))
      (node (ref "X8") (pin "A12") (pinfunction "A12_A12") (pintype "passive"))
      (node (ref "X9") (pin "A12") (pinfunction "A12_A12") (pintype "passive"))
    )
    (net (code "30") (name "/stby4") (class "Default")
      (node (ref "X0") (pin "20") (pinfunction "20_20") (pintype "passive"))
      (node (ref "X1") (pin "A13") (pinfunction "A13_A13") (pintype "passive"))
      (node (ref "X10") (pin "A13") (pinfunction "A13_A13") (pintype "passive"))
      (node (ref "X11") (pin "A13") (pinfunction "A13_A13") (pintype "passive"))
      (node (ref "X12") (pin "A13") (pinfunction "A13_A13") (pintype "passive"))
      (node (ref "X2") (pin "A13") (pinfunction "A13_A13") (pintype "passive"))
      (node (ref "X3") (pin "A13") (pinfunction "A13_A13") (pintype "passive"))
      (node (ref "X4") (pin "A13") (pinfunction "A13_A13") (pintype "passive"))
      (node (ref "X5") (pin "A13") (pinfunction "A13_A13") (pintype "passive"))
      (node (ref "X6") (pin "A13") (pinfunction "A13_A13") (pintype "passive"))
      (node (ref "X7") (pin "A13") (pinfunction "A13_A13") (pintype "passive"))
      (node (ref "X8") (pin "A13") (pinfunction "A13_A13") (pintype "passive"))
      (node (ref "X9") (pin "A13") (pinfunction "A13_A13") (pintype "passive"))
    )
    (net (code "31") (name "/stby5") (class "Default")
      (node (ref "X1") (pin "A14") (pinfunction "A14_A14") (pintype "passive"))
      (node (ref "X10") (pin "A14") (pinfunction "A14_A14") (pintype "passive"))
      (node (ref "X11") (pin "A14") (pinfunction "A14_A14") (pintype "passive"))
      (node (ref "X12") (pin "A14") (pinfunction "A14_A14") (pintype "passive"))
      (node (ref "X2") (pin "A14") (pinfunction "A14_A14") (pintype "passive"))
      (node (ref "X3") (pin "A14") (pinfunction "A14_A14") (pintype "passive"))
      (node (ref "X4") (pin "A14") (pinfunction "A14_A14") (pintype "passive"))
      (node (ref "X5") (pin "A14") (pinfunction "A14_A14") (pintype "passive"))
      (node (ref "X6") (pin "A14") (pinfunction "A14_A14") (pintype "passive"))
      (node (ref "X7") (pin "A14") (pinfunction "A14_A14") (pintype "passive"))
      (node (ref "X8") (pin "A14") (pinfunction "A14_A14") (pintype "passive"))
      (node (ref "X9") (pin "A14") (pinfunction "A14_A14") (pintype "passive"))
    )
    (net (code "32") (name "/stby6") (class "Default")
      (node (ref "X1") (pin "A15") (pinfunction "A15_A15") (pintype "passive"))
      (node (ref "X10") (pin "A15") (pinfunction "A15_A15") (pintype "passive"))
      (node (ref "X11") (pin "A15") (pinfunction "A15_A15") (pintype "passive"))
      (node (ref "X12") (pin "A15") (pinfunction "A15_A15") (pintype "passive"))
      (node (ref "X2") (pin "A15") (pinfunction "A15_A15") (pintype "passive"))
      (node (ref "X3") (pin "A15") (pinfunction "A15_A15") (pintype "passive"))
      (node (ref "X4") (pin "A15") (pinfunction "A15_A15") (pintype "passive"))
      (node (ref "X5") (pin "A15") (pinfunction "A15_A15") (pintype "passive"))
      (node (ref "X6") (pin "A15") (pinfunction "A15_A15") (pintype "passive"))
      (node (ref "X7") (pin "A15") (pinfunction "A15_A15") (pintype "passive"))
      (node (ref "X8") (pin "A15") (pinfunction "A15_A15") (pintype "passive"))
      (node (ref "X9") (pin "A15") (pinfunction "A15_A15") (pintype "passive"))
    )
    (net (code "33") (name "/stby7") (class "Default")
      (node (ref "X1") (pin "A16") (pinfunction "A16_A16") (pintype "passive"))
      (node (ref "X10") (pin "A16") (pinfunction "A16_A16") (pintype "passive"))
      (node (ref "X11") (pin "A16") (pinfunction "A16_A16") (pintype "passive"))
      (node (ref "X12") (pin "A16") (pinfunction "A16_A16") (pintype "passive"))
      (node (ref "X2") (pin "A16") (pinfunction "A16_A16") (pintype "passive"))
      (node (ref "X3") (pin "A16") (pinfunction "A16_A16") (pintype "passive"))
      (node (ref "X4") (pin "A16") (pinfunction "A16_A16") (pintype "passive"))
      (node (ref "X5") (pin "A16") (pinfunction "A16_A16") (pintype "passive"))
      (node (ref "X6") (pin "A16") (pinfunction "A16_A16") (pintype "passive"))
      (node (ref "X7") (pin "A16") (pinfunction "A16_A16") (pintype "passive"))
      (node (ref "X8") (pin "A16") (pinfunction "A16_A16") (pintype "passive"))
      (node (ref "X9") (pin "A16") (pinfunction "A16_A16") (pintype "passive"))
    )
    (net (code "34") (name "/stby8") (class "Default")
      (node (ref "X1") (pin "A17") (pinfunction "A17_A17") (pintype "passive"))
      (node (ref "X10") (pin "A17") (pinfunction "A17_A17") (pintype "passive"))
      (node (ref "X11") (pin "A17") (pinfunction "A17_A17") (pintype "passive"))
      (node (ref "X12") (pin "A17") (pinfunction "A17_A17") (pintype "passive"))
      (node (ref "X2") (pin "A17") (pinfunction "A17_A17") (pintype "passive"))
      (node (ref "X3") (pin "A17") (pinfunction "A17_A17") (pintype "passive"))
      (node (ref "X4") (pin "A17") (pinfunction "A17_A17") (pintype "passive"))
      (node (ref "X5") (pin "A17") (pinfunction "A17_A17") (pintype "passive"))
      (node (ref "X6") (pin "A17") (pinfunction "A17_A17") (pintype "passive"))
      (node (ref "X7") (pin "A17") (pinfunction "A17_A17") (pintype "passive"))
      (node (ref "X8") (pin "A17") (pinfunction "A17_A17") (pintype "passive"))
      (node (ref "X9") (pin "A17") (pinfunction "A17_A17") (pintype "passive"))
    )
    (net (code "35") (name "/stby9") (class "Default")
      (node (ref "X1") (pin "A19") (pinfunction "A19_A19") (pintype "passive"))
      (node (ref "X10") (pin "A19") (pinfunction "A19_A19") (pintype "passive"))
      (node (ref "X11") (pin "A19") (pinfunction "A19_A19") (pintype "passive"))
      (node (ref "X12") (pin "A19") (pinfunction "A19_A19") (pintype "passive"))
      (node (ref "X2") (pin "A19") (pinfunction "A19_A19") (pintype "passive"))
      (node (ref "X3") (pin "A19") (pinfunction "A19_A19") (pintype "passive"))
      (node (ref "X4") (pin "A19") (pinfunction "A19_A19") (pintype "passive"))
      (node (ref "X5") (pin "A19") (pinfunction "A19_A19") (pintype "passive"))
      (node (ref "X6") (pin "A19") (pinfunction "A19_A19") (pintype "passive"))
      (node (ref "X7") (pin "A19") (pinfunction "A19_A19") (pintype "passive"))
      (node (ref "X8") (pin "A19") (pinfunction "A19_A19") (pintype "passive"))
      (node (ref "X9") (pin "A19") (pinfunction "A19_A19") (pintype "passive"))
    )
    (net (code "36") (name "/stby10") (class "Default")
      (node (ref "X1") (pin "A20") (pinfunction "A20_A20") (pintype "passive"))
      (node (ref "X10") (pin "A20") (pinfunction "A20_A20") (pintype "passive"))
      (node (ref "X11") (pin "A20") (pinfunction "A20_A20") (pintype "passive"))
      (node (ref "X12") (pin "A20") (pinfunction "A20_A20") (pintype "passive"))
      (node (ref "X2") (pin "A20") (pinfunction "A20_A20") (pintype "passive"))
      (node (ref "X3") (pin "A20") (pinfunction "A20_A20") (pintype "passive"))
      (node (ref "X4") (pin "A20") (pinfunction "A20_A20") (pintype "passive"))
      (node (ref "X5") (pin "A20") (pinfunction "A20_A20") (pintype "passive"))
      (node (ref "X6") (pin "A20") (pinfunction "A20_A20") (pintype "passive"))
      (node (ref "X7") (pin "A20") (pinfunction "A20_A20") (pintype "passive"))
      (node (ref "X8") (pin "A20") (pinfunction "A20_A20") (pintype "passive"))
      (node (ref "X9") (pin "A20") (pinfunction "A20_A20") (pintype "passive"))
    )
    (net (code "37") (name "/stby11") (class "Default")
      (node (ref "X1") (pin "A21") (pinfunction "A21_A21") (pintype "passive"))
      (node (ref "X10") (pin "A21") (pinfunction "A21_A21") (pintype "passive"))
      (node (ref "X11") (pin "A21") (pinfunction "A21_A21") (pintype "passive"))
      (node (ref "X12") (pin "A21") (pinfunction "A21_A21") (pintype "passive"))
      (node (ref "X2") (pin "A21") (pinfunction "A21_A21") (pintype "passive"))
      (node (ref "X3") (pin "A21") (pinfunction "A21_A21") (pintype "passive"))
      (node (ref "X4") (pin "A21") (pinfunction "A21_A21") (pintype "passive"))
      (node (ref "X5") (pin "A21") (pinfunction "A21_A21") (pintype "passive"))
      (node (ref "X6") (pin "A21") (pinfunction "A21_A21") (pintype "passive"))
      (node (ref "X7") (pin "A21") (pinfunction "A21_A21") (pintype "passive"))
      (node (ref "X8") (pin "A21") (pinfunction "A21_A21") (pintype "passive"))
      (node (ref "X9") (pin "A21") (pinfunction "A21_A21") (pintype "passive"))
    )
    (net (code "38") (name "/stby12") (class "Default")
      (node (ref "X1") (pin "A22") (pinfunction "A22_A22") (pintype "passive"))
      (node (ref "X10") (pin "A22") (pinfunction "A22_A22") (pintype "passive"))
      (node (ref "X11") (pin "A22") (pinfunction "A22_A22") (pintype "passive"))
      (node (ref "X12") (pin "A22") (pinfunction "A22_A22") (pintype "passive"))
      (node (ref "X2") (pin "A22") (pinfunction "A22_A22") (pintype "passive"))
      (node (ref "X3") (pin "A22") (pinfunction "A22_A22") (pintype "passive"))
      (node (ref "X4") (pin "A22") (pinfunction "A22_A22") (pintype "passive"))
      (node (ref "X5") (pin "A22") (pinfunction "A22_A22") (pintype "passive"))
      (node (ref "X6") (pin "A22") (pinfunction "A22_A22") (pintype "passive"))
      (node (ref "X7") (pin "A22") (pinfunction "A22_A22") (pintype "passive"))
      (node (ref "X8") (pin "A22") (pinfunction "A22_A22") (pintype "passive"))
      (node (ref "X9") (pin "A22") (pinfunction "A22_A22") (pintype "passive"))
    )
    (net (code "39") (name "/stby13") (class "Default")
      (node (ref "X1") (pin "A23") (pinfunction "A23_A23") (pintype "passive"))
      (node (ref "X10") (pin "A23") (pinfunction "A23_A23") (pintype "passive"))
      (node (ref "X11") (pin "A23") (pinfunction "A23_A23") (pintype "passive"))
      (node (ref "X12") (pin "A23") (pinfunction "A23_A23") (pintype "passive"))
      (node (ref "X2") (pin "A23") (pinfunction "A23_A23") (pintype "passive"))
      (node (ref "X3") (pin "A23") (pinfunction "A23_A23") (pintype "passive"))
      (node (ref "X4") (pin "A23") (pinfunction "A23_A23") (pintype "passive"))
      (node (ref "X5") (pin "A23") (pinfunction "A23_A23") (pintype "passive"))
      (node (ref "X6") (pin "A23") (pinfunction "A23_A23") (pintype "passive"))
      (node (ref "X7") (pin "A23") (pinfunction "A23_A23") (pintype "passive"))
      (node (ref "X8") (pin "A23") (pinfunction "A23_A23") (pintype "passive"))
      (node (ref "X9") (pin "A23") (pinfunction "A23_A23") (pintype "passive"))
    )
    (net (code "40") (name "/stby14") (class "Default")
      (node (ref "X1") (pin "A24") (pinfunction "A24_A24") (pintype "passive"))
      (node (ref "X10") (pin "A24") (pinfunction "A24_A24") (pintype "passive"))
      (node (ref "X11") (pin "A24") (pinfunction "A24_A24") (pintype "passive"))
      (node (ref "X12") (pin "A24") (pinfunction "A24_A24") (pintype "passive"))
      (node (ref "X2") (pin "A24") (pinfunction "A24_A24") (pintype "passive"))
      (node (ref "X3") (pin "A24") (pinfunction "A24_A24") (pintype "passive"))
      (node (ref "X4") (pin "A24") (pinfunction "A24_A24") (pintype "passive"))
      (node (ref "X5") (pin "A24") (pinfunction "A24_A24") (pintype "passive"))
      (node (ref "X6") (pin "A24") (pinfunction "A24_A24") (pintype "passive"))
      (node (ref "X7") (pin "A24") (pinfunction "A24_A24") (pintype "passive"))
      (node (ref "X8") (pin "A24") (pinfunction "A24_A24") (pintype "passive"))
      (node (ref "X9") (pin "A24") (pinfunction "A24_A24") (pintype "passive"))
    )
    (net (code "41") (name "/stby15") (class "Default")
      (node (ref "X1") (pin "A26") (pinfunction "A26_A26") (pintype "passive"))
      (node (ref "X10") (pin "A26") (pinfunction "A26_A26") (pintype "passive"))
      (node (ref "X11") (pin "A26") (pinfunction "A26_A26") (pintype "passive"))
      (node (ref "X12") (pin "A26") (pinfunction "A26_A26") (pintype "passive"))
      (node (ref "X2") (pin "A26") (pinfunction "A26_A26") (pintype "passive"))
      (node (ref "X3") (pin "A26") (pinfunction "A26_A26") (pintype "passive"))
      (node (ref "X4") (pin "A26") (pinfunction "A26_A26") (pintype "passive"))
      (node (ref "X5") (pin "A26") (pinfunction "A26_A26") (pintype "passive"))
      (node (ref "X6") (pin "A26") (pinfunction "A26_A26") (pintype "passive"))
      (node (ref "X7") (pin "A26") (pinfunction "A26_A26") (pintype "passive"))
      (node (ref "X8") (pin "A26") (pinfunction "A26_A26") (pintype "passive"))
      (node (ref "X9") (pin "A26") (pinfunction "A26_A26") (pintype "passive"))
    )
    (net (code "42") (name "/stby16") (class "Default")
      (node (ref "X1") (pin "A27") (pinfunction "A27_A27") (pintype "passive"))
      (node (ref "X10") (pin "A27") (pinfunction "A27_A27") (pintype "passive"))
      (node (ref "X11") (pin "A27") (pinfunction "A27_A27") (pintype "passive"))
      (node (ref "X12") (pin "A27") (pinfunction "A27_A27") (pintype "passive"))
      (node (ref "X2") (pin "A27") (pinfunction "A27_A27") (pintype "passive"))
      (node (ref "X3") (pin "A27") (pinfunction "A27_A27") (pintype "passive"))
      (node (ref "X4") (pin "A27") (pinfunction "A27_A27") (pintype "passive"))
      (node (ref "X5") (pin "A27") (pinfunction "A27_A27") (pintype "passive"))
      (node (ref "X6") (pin "A27") (pinfunction "A27_A27") (pintype "passive"))
      (node (ref "X7") (pin "A27") (pinfunction "A27_A27") (pintype "passive"))
      (node (ref "X8") (pin "A27") (pinfunction "A27_A27") (pintype "passive"))
      (node (ref "X9") (pin "A27") (pinfunction "A27_A27") (pintype "passive"))
    )
    (net (code "43") (name "/stby17") (class "Default")
      (node (ref "X1") (pin "A28") (pinfunction "A28_A28") (pintype "passive"))
      (node (ref "X10") (pin "A28") (pinfunction "A28_A28") (pintype "passive"))
      (node (ref "X11") (pin "A28") (pinfunction "A28_A28") (pintype "passive"))
      (node (ref "X12") (pin "A28") (pinfunction "A28_A28") (pintype "passive"))
      (node (ref "X2") (pin "A28") (pinfunction "A28_A28") (pintype "passive"))
      (node (ref "X3") (pin "A28") (pinfunction "A28_A28") (pintype "passive"))
      (node (ref "X4") (pin "A28") (pinfunction "A28_A28") (pintype "passive"))
      (node (ref "X5") (pin "A28") (pinfunction "A28_A28") (pintype "passive"))
      (node (ref "X6") (pin "A28") (pinfunction "A28_A28") (pintype "passive"))
      (node (ref "X7") (pin "A28") (pinfunction "A28_A28") (pintype "passive"))
      (node (ref "X8") (pin "A28") (pinfunction "A28_A28") (pintype "passive"))
      (node (ref "X9") (pin "A28") (pinfunction "A28_A28") (pintype "passive"))
    )
    (net (code "44") (name "/time") (class "Default")
      (node (ref "X1") (pin "A29") (pinfunction "A29_A29") (pintype "passive"))
      (node (ref "X10") (pin "A29") (pinfunction "A29_A29") (pintype "passive"))
      (node (ref "X11") (pin "A29") (pinfunction "A29_A29") (pintype "passive"))
      (node (ref "X12") (pin "A29") (pinfunction "A29_A29") (pintype "passive"))
      (node (ref "X2") (pin "A29") (pinfunction "A29_A29") (pintype "passive"))
      (node (ref "X3") (pin "A29") (pinfunction "A29_A29") (pintype "passive"))
      (node (ref "X4") (pin "A29") (pinfunction "A29_A29") (pintype "passive"))
      (node (ref "X5") (pin "A29") (pinfunction "A29_A29") (pintype "passive"))
      (node (ref "X6") (pin "A29") (pinfunction "A29_A29") (pintype "passive"))
      (node (ref "X7") (pin "A29") (pinfunction "A29_A29") (pintype "passive"))
      (node (ref "X8") (pin "A29") (pinfunction "A29_A29") (pintype "passive"))
      (node (ref "X9") (pin "A29") (pinfunction "A29_A29") (pintype "passive"))
    )
    (net (code "45") (name "GND") (class "Default")
      (node (ref "R1") (pin "2") (pinfunction "2_2") (pintype "passive"))
      (node (ref "X0") (pin "5") (pinfunction "5_5") (pintype "passive"))
      (node (ref "X0") (pin "6") (pinfunction "6_6") (pintype "passive"))
      (node (ref "X0") (pin "7") (pinfunction "7_7") (pintype "passive"))
      (node (ref "X0") (pin "8") (pinfunction "8_8") (pintype "passive"))
      (node (ref "X1") (pin "A11") (pinfunction "A11_A11") (pintype "passive"))
      (node (ref "X1") (pin "A18") (pinfunction "A18_A18") (pintype "passive"))
      (node (ref "X1") (pin "A25") (pinfunction "A25_A25") (pintype "passive"))
      (node (ref "X1") (pin "A3") (pinfunction "A3_A3") (pintype "passive"))
      (node (ref "X1") (pin "A32") (pinfunction "A32_A32") (pintype "passive"))
      (node (ref "X1") (pin "A4") (pinfunction "A4_A4") (pintype "passive"))
      (node (ref "X1") (pin "B11") (pinfunction "B11_B11") (pintype "passive"))
      (node (ref "X1") (pin "B18") (pinfunction "B18_B18") (pintype "passive"))
      (node (ref "X1") (pin "B25") (pinfunction "B25_B25") (pintype "passive"))
      (node (ref "X1") (pin "B3") (pinfunction "B3_B3") (pintype "passive"))
      (node (ref "X1") (pin "B32") (pinfunction "B32_B32") (pintype "passive"))
      (node (ref "X1") (pin "B4") (pinfunction "B4_B4") (pintype "passive"))
      (node (ref "X1") (pin "C11") (pinfunction "C11_C11") (pintype "passive"))
      (node (ref "X1") (pin "C18") (pinfunction "C18_C18") (pintype "passive"))
      (node (ref "X1") (pin "C25") (pinfunction "C25_C25") (pintype "passive"))
      (node (ref "X1") (pin "C3") (pinfunction "C3_C3") (pintype "passive"))
      (node (ref "X1") (pin "C32") (pinfunction "C32_C32") (pintype "passive"))
      (node (ref "X1") (pin "C4") (pinfunction "C4_C4") (pintype "passive"))
      (node (ref "X10") (pin "A11") (pinfunction "A11_A11") (pintype "passive"))
      (node (ref "X10") (pin "A18") (pinfunction "A18_A18") (pintype "passive"))
      (node (ref "X10") (pin "A25") (pinfunction "A25_A25") (pintype "passive"))
      (node (ref "X10") (pin "A3") (pinfunction "A3_A3") (pintype "passive"))
      (node (ref "X10") (pin "A32") (pinfunction "A32_A32") (pintype "passive"))
      (node (ref "X10") (pin "A4") (pinfunction "A4_A4") (pintype "passive"))
      (node (ref "X10") (pin "B11") (pinfunction "B11_B11") (pintype "passive"))
      (node (ref "X10") (pin "B18") (pinfunction "B18_B18") (pintype "passive"))
      (node (ref "X10") (pin "B25") (pinfunction "B25_B25") (pintype "passive"))
      (node (ref "X10") (pin "B3") (pinfunction "B3_B3") (pintype "passive"))
      (node (ref "X10") (pin "B32") (pinfunction "B32_B32") (pintype "passive"))
      (node (ref "X10") (pin "B4") (pinfunction "B4_B4") (pintype "passive"))
      (node (ref "X10") (pin "C11") (pinfunction "C11_C11") (pintype "passive"))
      (node (ref "X10") (pin "C18") (pinfunction "C18_C18") (pintype "passive"))
      (node (ref "X10") (pin "C25") (pinfunction "C25_C25") (pintype "passive"))
      (node (ref "X10") (pin "C3") (pinfunction "C3_C3") (pintype "passive"))
      (node (ref "X10") (pin "C32") (pinfunction "C32_C32") (pintype "passive"))
      (node (ref "X10") (pin "C4") (pinfunction "C4_C4") (pintype "passive"))
      (node (ref "X11") (pin "A11") (pinfunction "A11_A11") (pintype "passive"))
      (node (ref "X11") (pin "A18") (pinfunction "A18_A18") (pintype "passive"))
      (node (ref "X11") (pin "A25") (pinfunction "A25_A25") (pintype "passive"))
      (node (ref "X11") (pin "A3") (pinfunction "A3_A3") (pintype "passive"))
      (node (ref "X11") (pin "A32") (pinfunction "A32_A32") (pintype "passive"))
      (node (ref "X11") (pin "A4") (pinfunction "A4_A4") (pintype "passive"))
      (node (ref "X11") (pin "B11") (pinfunction "B11_B11") (pintype "passive"))
      (node (ref "X11") (pin "B18") (pinfunction "B18_B18") (pintype "passive"))
      (node (ref "X11") (pin "B25") (pinfunction "B25_B25") (pintype "passive"))
      (node (ref "X11") (pin "B3") (pinfunction "B3_B3") (pintype "passive"))
      (node (ref "X11") (pin "B32") (pinfunction "B32_B32") (pintype "passive"))
      (node (ref "X11") (pin "B4") (pinfunction "B4_B4") (pintype "passive"))
      (node (ref "X11") (pin "C11") (pinfunction "C11_C11") (pintype "passive"))
      (node (ref "X11") (pin "C18") (pinfunction "C18_C18") (pintype "passive"))
      (node (ref "X11") (pin "C25") (pinfunction "C25_C25") (pintype "passive"))
      (node (ref "X11") (pin "C3") (pinfunction "C3_C3") (pintype "passive"))
      (node (ref "X11") (pin "C32") (pinfunction "C32_C32") (pintype "passive"))
      (node (ref "X11") (pin "C4") (pinfunction "C4_C4") (pintype "passive"))
      (node (ref "X12") (pin "A11") (pinfunction "A11_A11") (pintype "passive"))
      (node (ref "X12") (pin "A18") (pinfunction "A18_A18") (pintype "passive"))
      (node (ref "X12") (pin "A25") (pinfunction "A25_A25") (pintype "passive"))
      (node (ref "X12") (pin "A3") (pinfunction "A3_A3") (pintype "passive"))
      (node (ref "X12") (pin "A32") (pinfunction "A32_A32") (pintype "passive"))
      (node (ref "X12") (pin "A4") (pinfunction "A4_A4") (pintype "passive"))
      (node (ref "X12") (pin "B11") (pinfunction "B11_B11") (pintype "passive"))
      (node (ref "X12") (pin "B18") (pinfunction "B18_B18") (pintype "passive"))
      (node (ref "X12") (pin "B25") (pinfunction "B25_B25") (pintype "passive"))
      (node (ref "X12") (pin "B3") (pinfunction "B3_B3") (pintype "passive"))
      (node (ref "X12") (pin "B32") (pinfunction "B32_B32") (pintype "passive"))
      (node (ref "X12") (pin "B4") (pinfunction "B4_B4") (pintype "passive"))
      (node (ref "X12") (pin "C11") (pinfunction "C11_C11") (pintype "passive"))
      (node (ref "X12") (pin "C18") (pinfunction "C18_C18") (pintype "passive"))
      (node (ref "X12") (pin "C25") (pinfunction "C25_C25") (pintype "passive"))
      (node (ref "X12") (pin "C3") (pinfunction "C3_C3") (pintype "passive"))
      (node (ref "X12") (pin "C32") (pinfunction "C32_C32") (pintype "passive"))
      (node (ref "X12") (pin "C4") (pinfunction "C4_C4") (pintype "passive"))
      (node (ref "X2") (pin "A11") (pinfunction "A11_A11") (pintype "passive"))
      (node (ref "X2") (pin "A18") (pinfunction "A18_A18") (pintype "passive"))
      (node (ref "X2") (pin "A25") (pinfunction "A25_A25") (pintype "passive"))
      (node (ref "X2") (pin "A3") (pinfunction "A3_A3") (pintype "passive"))
      (node (ref "X2") (pin "A32") (pinfunction "A32_A32") (pintype "passive"))
      (node (ref "X2") (pin "A4") (pinfunction "A4_A4") (pintype "passive"))
      (node (ref "X2") (pin "B11") (pinfunction "B11_B11") (pintype "passive"))
      (node (ref "X2") (pin "B18") (pinfunction "B18_B18") (pintype "passive"))
      (node (ref "X2") (pin "B25") (pinfunction "B25_B25") (pintype "passive"))
      (node (ref "X2") (pin "B3") (pinfunction "B3_B3") (pintype "passive"))
      (node (ref "X2") (pin "B32") (pinfunction "B32_B32") (pintype "passive"))
      (node (ref "X2") (pin "B4") (pinfunction "B4_B4") (pintype "passive"))
      (node (ref "X2") (pin "C11") (pinfunction "C11_C11") (pintype "passive"))
      (node (ref "X2") (pin "C18") (pinfunction "C18_C18") (pintype "passive"))
      (node (ref "X2") (pin "C25") (pinfunction "C25_C25") (pintype "passive"))
      (node (ref "X2") (pin "C3") (pinfunction "C3_C3") (pintype "passive"))
      (node (ref "X2") (pin "C32") (pinfunction "C32_C32") (pintype "passive"))
      (node (ref "X2") (pin "C4") (pinfunction "C4_C4") (pintype "passive"))
      (node (ref "X3") (pin "A11") (pinfunction "A11_A11") (pintype "passive"))
      (node (ref "X3") (pin "A18") (pinfunction "A18_A18") (pintype "passive"))
      (node (ref "X3") (pin "A25") (pinfunction "A25_A25") (pintype "passive"))
      (node (ref "X3") (pin "A3") (pinfunction "A3_A3") (pintype "passive"))
      (node (ref "X3") (pin "A32") (pinfunction "A32_A32") (pintype "passive"))
      (node (ref "X3") (pin "A4") (pinfunction "A4_A4") (pintype "passive"))
      (node (ref "X3") (pin "B11") (pinfunction "B11_B11") (pintype "passive"))
      (node (ref "X3") (pin "B18") (pinfunction "B18_B18") (pintype "passive"))
      (node (ref "X3") (pin "B25") (pinfunction "B25_B25") (pintype "passive"))
      (node (ref "X3") (pin "B3") (pinfunction "B3_B3") (pintype "passive"))
      (node (ref "X3") (pin "B32") (pinfunction "B32_B32") (pintype "passive"))
      (node (ref "X3") (pin "B4") (pinfunction "B4_B4") (pintype "passive"))
      (node (ref "X3") (pin "C11") (pinfunction "C11_C11") (pintype "passive"))
      (node (ref "X3") (pin "C18") (pinfunction "C18_C18") (pintype "passive"))
      (node (ref "X3") (pin "C25") (pinfunction "C25_C25") (pintype "passive"))
      (node (ref "X3") (pin "C3") (pinfunction "C3_C3") (pintype "passive"))
      (node (ref "X3") (pin "C32") (pinfunction "C32_C32") (pintype "passive"))
      (node (ref "X3") (pin "C4") (pinfunction "C4_C4") (pintype "passive"))
      (node (ref "X4") (pin "A11") (pinfunction "A11_A11") (pintype "passive"))
      (node (ref "X4") (pin "A18") (pinfunction "A18_A18") (pintype "passive"))
      (node (ref "X4") (pin "A25") (pinfunction "A25_A25") (pintype "passive"))
      (node (ref "X4") (pin "A3") (pinfunction "A3_A3") (pintype "passive"))
      (node (ref "X4") (pin "A32") (pinfunction "A32_A32") (pintype "passive"))
      (node (ref "X4") (pin "A4") (pinfunction "A4_A4") (pintype "passive"))
      (node (ref "X4") (pin "B11") (pinfunction "B11_B11") (pintype "passive"))
      (node (ref "X4") (pin "B18") (pinfunction "B18_B18") (pintype "passive"))
      (node (ref "X4") (pin "B25") (pinfunction "B25_B25") (pintype "passive"))
      (node (ref "X4") (pin "B3") (pinfunction "B3_B3") (pintype "passive"))
      (node (ref "X4") (pin "B32") (pinfunction "B32_B32") (pintype "passive"))
      (node (ref "X4") (pin "B4") (pinfunction "B4_B4") (pintype "passive"))
      (node (ref "X4") (pin "C11") (pinfunction "C11_C11") (pintype "passive"))
      (node (ref "X4") (pin "C18") (pinfunction "C18_C18") (pintype "passive"))
      (node (ref "X4") (pin "C25") (pinfunction "C25_C25") (pintype "passive"))
      (node (ref "X4") (pin "C3") (pinfunction "C3_C3") (pintype "passive"))
      (node (ref "X4") (pin "C32") (pinfunction "C32_C32") (pintype "passive"))
      (node (ref "X4") (pin "C4") (pinfunction "C4_C4") (pintype "passive"))
      (node (ref "X5") (pin "A11") (pinfunction "A11_A11") (pintype "passive"))
      (node (ref "X5") (pin "A18") (pinfunction "A18_A18") (pintype "passive"))
      (node (ref "X5") (pin "A25") (pinfunction "A25_A25") (pintype "passive"))
      (node (ref "X5") (pin "A3") (pinfunction "A3_A3") (pintype "passive"))
      (node (ref "X5") (pin "A32") (pinfunction "A32_A32") (pintype "passive"))
      (node (ref "X5") (pin "A4") (pinfunction "A4_A4") (pintype "passive"))
      (node (ref "X5") (pin "B11") (pinfunction "B11_B11") (pintype "passive"))
      (node (ref "X5") (pin "B18") (pinfunction "B18_B18") (pintype "passive"))
      (node (ref "X5") (pin "B25") (pinfunction "B25_B25") (pintype "passive"))
      (node (ref "X5") (pin "B3") (pinfunction "B3_B3") (pintype "passive"))
      (node (ref "X5") (pin "B32") (pinfunction "B32_B32") (pintype "passive"))
      (node (ref "X5") (pin "B4") (pinfunction "B4_B4") (pintype "passive"))
      (node (ref "X5") (pin "C11") (pinfunction "C11_C11") (pintype "passive"))
      (node (ref "X5") (pin "C18") (pinfunction "C18_C18") (pintype "passive"))
      (node (ref "X5") (pin "C25") (pinfunction "C25_C25") (pintype "passive"))
      (node (ref "X5") (pin "C3") (pinfunction "C3_C3") (pintype "passive"))
      (node (ref "X5") (pin "C32") (pinfunction "C32_C32") (pintype "passive"))
      (node (ref "X5") (pin "C4") (pinfunction "C4_C4") (pintype "passive"))
      (node (ref "X6") (pin "A11") (pinfunction "A11_A11") (pintype "passive"))
      (node (ref "X6") (pin "A18") (pinfunction "A18_A18") (pintype "passive"))
      (node (ref "X6") (pin "A25") (pinfunction "A25_A25") (pintype "passive"))
      (node (ref "X6") (pin "A3") (pinfunction "A3_A3") (pintype "passive"))
      (node (ref "X6") (pin "A32") (pinfunction "A32_A32") (pintype "passive"))
      (node (ref "X6") (pin "A4") (pinfunction "A4_A4") (pintype "passive"))
      (node (ref "X6") (pin "B11") (pinfunction "B11_B11") (pintype "passive"))
      (node (ref "X6") (pin "B18") (pinfunction "B18_B18") (pintype "passive"))
      (node (ref "X6") (pin "B25") (pinfunction "B25_B25") (pintype "passive"))
      (node (ref "X6") (pin "B3") (pinfunction "B3_B3") (pintype "passive"))
      (node (ref "X6") (pin "B32") (pinfunction "B32_B32") (pintype "passive"))
      (node (ref "X6") (pin "B4") (pinfunction "B4_B4") (pintype "passive"))
      (node (ref "X6") (pin "C11") (pinfunction "C11_C11") (pintype "passive"))
      (node (ref "X6") (pin "C18") (pinfunction "C18_C18") (pintype "passive"))
      (node (ref "X6") (pin "C25") (pinfunction "C25_C25") (pintype "passive"))
      (node (ref "X6") (pin "C3") (pinfunction "C3_C3") (pintype "passive"))
      (node (ref "X6") (pin "C32") (pinfunction "C32_C32") (pintype "passive"))
      (node (ref "X6") (pin "C4") (pinfunction "C4_C4") (pintype "passive"))
      (node (ref "X7") (pin "A11") (pinfunction "A11_A11") (pintype "passive"))
      (node (ref "X7") (pin "A18") (pinfunction "A18_A18") (pintype "passive"))
      (node (ref "X7") (pin "A25") (pinfunction "A25_A25") (pintype "passive"))
      (node (ref "X7") (pin "A3") (pinfunction "A3_A3") (pintype "passive"))
      (node (ref "X7") (pin "A4") (pinfunction "A4_A4") (pintype "passive"))
      (node (ref "X7") (pin "B11") (pinfunction "B11_B11") (pintype "passive"))
      (node (ref "X7") (pin "B18") (pinfunction "B18_B18") (pintype "passive"))
      (node (ref "X7") (pin "B25") (pinfunction "B25_B25") (pintype "passive"))
      (node (ref "X7") (pin "B3") (pinfunction "B3_B3") (pintype "passive"))
      (node (ref "X7") (pin "B30") (pinfunction "B30_B30") (pintype "passive"))
      (node (ref "X7") (pin "B4") (pinfunction "B4_B4") (pintype "passive"))
      (node (ref "X7") (pin "C11") (pinfunction "C11_C11") (pintype "passive"))
      (node (ref "X7") (pin "C18") (pinfunction "C18_C18") (pintype "passive"))
      (node (ref "X7") (pin "C25") (pinfunction "C25_C25") (pintype "passive"))
      (node (ref "X7") (pin "C3") (pinfunction "C3_C3") (pintype "passive"))
      (node (ref "X7") (pin "C4") (pinfunction "C4_C4") (pintype "passive"))
      (node (ref "X8") (pin "A11") (pinfunction "A11_A11") (pintype "passive"))
      (node (ref "X8") (pin "A18") (pinfunction "A18_A18") (pintype "passive"))
      (node (ref "X8") (pin "A25") (pinfunction "A25_A25") (pintype "passive"))
      (node (ref "X8") (pin "A3") (pinfunction "A3_A3") (pintype "passive"))
      (node (ref "X8") (pin "A4") (pinfunction "A4_A4") (pintype "passive"))
      (node (ref "X8") (pin "B11") (pinfunction "B11_B11") (pintype "passive"))
      (node (ref "X8") (pin "B18") (pinfunction "B18_B18") (pintype "passive"))
      (node (ref "X8") (pin "B25") (pinfunction "B25_B25") (pintype "passive"))
      (node (ref "X8") (pin "B3") (pinfunction "B3_B3") (pintype "passive"))
      (node (ref "X8") (pin "B30") (pinfunction "B30_B30") (pintype "passive"))
      (node (ref "X8") (pin "B4") (pinfunction "B4_B4") (pintype "passive"))
      (node (ref "X8") (pin "C11") (pinfunction "C11_C11") (pintype "passive"))
      (node (ref "X8") (pin "C18") (pinfunction "C18_C18") (pintype "passive"))
      (node (ref "X8") (pin "C25") (pinfunction "C25_C25") (pintype "passive"))
      (node (ref "X8") (pin "C3") (pinfunction "C3_C3") (pintype "passive"))
      (node (ref "X8") (pin "C4") (pinfunction "C4_C4") (pintype "passive"))
      (node (ref "X9") (pin "A11") (pinfunction "A11_A11") (pintype "passive"))
      (node (ref "X9") (pin "A18") (pinfunction "A18_A18") (pintype "passive"))
      (node (ref "X9") (pin "A25") (pinfunction "A25_A25") (pintype "passive"))
      (node (ref "X9") (pin "A3") (pinfunction "A3_A3") (pintype "passive"))
      (node (ref "X9") (pin "A32") (pinfunction "A32_A32") (pintype "passive"))
      (node (ref "X9") (pin "A4") (pinfunction "A4_A4") (pintype "passive"))
      (node (ref "X9") (pin "B11") (pinfunction "B11_B11") (pintype "passive"))
      (node (ref "X9") (pin "B18") (pinfunction "B18_B18") (pintype "passive"))
      (node (ref "X9") (pin "B25") (pinfunction "B25_B25") (pintype "passive"))
      (node (ref "X9") (pin "B3") (pinfunction "B3_B3") (pintype "passive"))
      (node (ref "X9") (pin "B32") (pinfunction "B32_B32") (pintype "passive"))
      (node (ref "X9") (pin "B4") (pinfunction "B4_B4") (pintype "passive"))
      (node (ref "X9") (pin "C11") (pinfunction "C11_C11") (pintype "passive"))
      (node (ref "X9") (pin "C18") (pinfunction "C18_C18") (pintype "passive"))
      (node (ref "X9") (pin "C25") (pinfunction "C25_C25") (pintype "passive"))
      (node (ref "X9") (pin "C3") (pinfunction "C3_C3") (pintype "passive"))
      (node (ref "X9") (pin "C32") (pinfunction "C32_C32") (pintype "passive"))
      (node (ref "X9") (pin "C4") (pinfunction "C4_C4") (pintype "passive"))
    )
    (net (code "46") (name "PE") (class "Default")
      (node (ref "X7") (pin "A31") (pinfunction "A31_A31") (pintype "passive"))
      (node (ref "X7") (pin "A32") (pinfunction "A32_A32") (pintype "passive"))
      (node (ref "X7") (pin "B31") (pinfunction "B31_B31") (pintype "passive"))
      (node (ref "X7") (pin "B32") (pinfunction "B32_B32") (pintype "passive"))
      (node (ref "X7") (pin "C32") (pinfunction "C32_C32") (pintype "passive"))
      (node (ref "X8") (pin "A31") (pinfunction "A31_A31") (pintype "passive"))
      (node (ref "X8") (pin "A32") (pinfunction "A32_A32") (pintype "passive"))
      (node (ref "X8") (pin "B31") (pinfunction "B31_B31") (pintype "passive"))
      (node (ref "X8") (pin "B32") (pinfunction "B32_B32") (pintype "passive"))
      (node (ref "X8") (pin "C32") (pinfunction "C32_C32") (pintype "passive"))
    )
    (net (code "47") (name "unconnected-(X1-Pad97)") (class "Default")
      (node (ref "X1") (pin "97") (pinfunction "97_97") (pintype "passive"))
    )
    (net (code "48") (name "unconnected-(X1-Pad98)") (class "Default")
      (node (ref "X1") (pin "98") (pinfunction "98_98") (pintype "passive"))
    )
    (net (code "49") (name "unconnected-(X1-PadA31)") (class "Default")
      (node (ref "X1") (pin "A31") (pinfunction "A31_A31") (pintype "passive"))
    )
    (net (code "50") (name "unconnected-(X1-PadB5)") (class "Default")
      (node (ref "X1") (pin "B5") (pinfunction "B5_B5") (pintype "passive"))
    )
    (net (code "51") (name "unconnected-(X1-PadB6)") (class "Default")
      (node (ref "X1") (pin "B6") (pinfunction "B6_B6") (pintype "passive"))
    )
    (net (code "52") (name "unconnected-(X1-PadB7)") (class "Default")
      (node (ref "X1") (pin "B7") (pinfunction "B7_B7") (pintype "passive"))
    )
    (net (code "53") (name "unconnected-(X1-PadB8)") (class "Default")
      (node (ref "X1") (pin "B8") (pinfunction "B8_B8") (pintype "passive"))
    )
    (net (code "54") (name "unconnected-(X1-PadB9)") (class "Default")
      (node (ref "X1") (pin "B9") (pinfunction "B9_B9") (pintype "passive"))
    )
    (net (code "55") (name "unconnected-(X1-PadB10)") (class "Default")
      (node (ref "X1") (pin "B10") (pinfunction "B10_B10") (pintype "passive"))
    )
    (net (code "56") (name "unconnected-(X1-PadB12)") (class "Default")
      (node (ref "X1") (pin "B12") (pinfunction "B12_B12") (pintype "passive"))
    )
    (net (code "57") (name "unconnected-(X1-PadB13)") (class "Default")
      (node (ref "X1") (pin "B13") (pinfunction "B13_B13") (pintype "passive"))
    )
    (net (code "58") (name "unconnected-(X1-PadB14)") (class "Default")
      (node (ref "X1") (pin "B14") (pinfunction "B14_B14") (pintype "passive"))
    )
    (net (code "59") (name "unconnected-(X1-PadB15)") (class "Default")
      (node (ref "X1") (pin "B15") (pinfunction "B15_B15") (pintype "passive"))
    )
    (net (code "60") (name "unconnected-(X1-PadB16)") (class "Default")
      (node (ref "X1") (pin "B16") (pinfunction "B16_B16") (pintype "passive"))
    )
    (net (code "61") (name "unconnected-(X1-PadB17)") (class "Default")
      (node (ref "X1") (pin "B17") (pinfunction "B17_B17") (pintype "passive"))
    )
    (net (code "62") (name "unconnected-(X1-PadB19)") (class "Default")
      (node (ref "X1") (pin "B19") (pinfunction "B19_B19") (pintype "passive"))
    )
    (net (code "63") (name "unconnected-(X1-PadB20)") (class "Default")
      (node (ref "X1") (pin "B20") (pinfunction "B20_B20") (pintype "passive"))
    )
    (net (code "64") (name "unconnected-(X1-PadB21)") (class "Default")
      (node (ref "X1") (pin "B21") (pinfunction "B21_B21") (pintype "passive"))
    )
    (net (code "65") (name "unconnected-(X1-PadB22)") (class "Default")
      (node (ref "X1") (pin "B22") (pinfunction "B22_B22") (pintype "passive"))
    )
    (net (code "66") (name "unconnected-(X1-PadB23)") (class "Default")
      (node (ref "X1") (pin "B23") (pinfunction "B23_B23") (pintype "passive"))
    )
    (net (code "67") (name "unconnected-(X1-PadB24)") (class "Default")
      (node (ref "X1") (pin "B24") (pinfunction "B24_B24") (pintype "passive"))
    )
    (net (code "68") (name "unconnected-(X1-PadB26)") (class "Default")
      (node (ref "X1") (pin "B26") (pinfunction "B26_B26") (pintype "passive"))
    )
    (net (code "69") (name "unconnected-(X1-PadB27)") (class "Default")
      (node (ref "X1") (pin "B27") (pinfunction "B27_B27") (pintype "passive"))
    )
    (net (code "70") (name "unconnected-(X1-PadB28)") (class "Default")
      (node (ref "X1") (pin "B28") (pinfunction "B28_B28") (pintype "passive"))
    )
    (net (code "71") (name "unconnected-(X1-PadB29)") (class "Default")
      (node (ref "X1") (pin "B29") (pinfunction "B29_B29") (pintype "passive"))
    )
    (net (code "72") (name "unconnected-(X1-PadB30)") (class "Default")
      (node (ref "X1") (pin "B30") (pinfunction "B30_B30") (pintype "passive"))
    )
    (net (code "73") (name "unconnected-(X1-PadB31)") (class "Default")
      (node (ref "X1") (pin "B31") (pinfunction "B31_B31") (pintype "passive"))
    )
    (net (code "74") (name "unconnected-(X2-Pad97)") (class "Default")
      (node (ref "X2") (pin "97") (pinfunction "97_97") (pintype "passive"))
    )
    (net (code "75") (name "unconnected-(X2-Pad98)") (class "Default")
      (node (ref "X2") (pin "98") (pinfunction "98_98") (pintype "passive"))
    )
    (net (code "76") (name "unconnected-(X2-PadA31)") (class "Default")
      (node (ref "X2") (pin "A31") (pinfunction "A31_A31") (pintype "passive"))
    )
    (net (code "77") (name "unconnected-(X2-PadB5)") (class "Default")
      (node (ref "X2") (pin "B5") (pinfunction "B5_B5") (pintype "passive"))
    )
    (net (code "78") (name "unconnected-(X2-PadB6)") (class "Default")
      (node (ref "X2") (pin "B6") (pinfunction "B6_B6") (pintype "passive"))
    )
    (net (code "79") (name "unconnected-(X2-PadB7)") (class "Default")
      (node (ref "X2") (pin "B7") (pinfunction "B7_B7") (pintype "passive"))
    )
    (net (code "80") (name "unconnected-(X2-PadB8)") (class "Default")
      (node (ref "X2") (pin "B8") (pinfunction "B8_B8") (pintype "passive"))
    )
    (net (code "81") (name "unconnected-(X2-PadB9)") (class "Default")
      (node (ref "X2") (pin "B9") (pinfunction "B9_B9") (pintype "passive"))
    )
    (net (code "82") (name "unconnected-(X2-PadB10)") (class "Default")
      (node (ref "X2") (pin "B10") (pinfunction "B10_B10") (pintype "passive"))
    )
    (net (code "83") (name "unconnected-(X2-PadB12)") (class "Default")
      (node (ref "X2") (pin "B12") (pinfunction "B12_B12") (pintype "passive"))
    )
    (net (code "84") (name "unconnected-(X2-PadB13)") (class "Default")
      (node (ref "X2") (pin "B13") (pinfunction "B13_B13") (pintype "passive"))
    )
    (net (code "85") (name "unconnected-(X2-PadB14)") (class "Default")
      (node (ref "X2") (pin "B14") (pinfunction "B14_B14") (pintype "passive"))
    )
    (net (code "86") (name "unconnected-(X2-PadB15)") (class "Default")
      (node (ref "X2") (pin "B15") (pinfunction "B15_B15") (pintype "passive"))
    )
    (net (code "87") (name "unconnected-(X2-PadB16)") (class "Default")
      (node (ref "X2") (pin "B16") (pinfunction "B16_B16") (pintype "passive"))
    )
    (net (code "88") (name "unconnected-(X2-PadB17)") (class "Default")
      (node (ref "X2") (pin "B17") (pinfunction "B17_B17") (pintype "passive"))
    )
    (net (code "89") (name "unconnected-(X2-PadB19)") (class "Default")
      (node (ref "X2") (pin "B19") (pinfunction "B19_B19") (pintype "passive"))
    )
    (net (code "90") (name "unconnected-(X2-PadB20)") (class "Default")
      (node (ref "X2") (pin "B20") (pinfunction "B20_B20") (pintype "passive"))
    )
    (net (code "91") (name "unconnected-(X2-PadB21)") (class "Default")
      (node (ref "X2") (pin "B21") (pinfunction "B21_B21") (pintype "passive"))
    )
    (net (code "92") (name "unconnected-(X2-PadB22)") (class "Default")
      (node (ref "X2") (pin "B22") (pinfunction "B22_B22") (pintype "passive"))
    )
    (net (code "93") (name "unconnected-(X2-PadB23)") (class "Default")
      (node (ref "X2") (pin "B23") (pinfunction "B23_B23") (pintype "passive"))
    )
    (net (code "94") (name "unconnected-(X2-PadB24)") (class "Default")
      (node (ref "X2") (pin "B24") (pinfunction "B24_B24") (pintype "passive"))
    )
    (net (code "95") (name "unconnected-(X2-PadB26)") (class "Default")
      (node (ref "X2") (pin "B26") (pinfunction "B26_B26") (pintype "passive"))
    )
    (net (code "96") (name "unconnected-(X2-PadB27)") (class "Default")
      (node (ref "X2") (pin "B27") (pinfunction "B27_B27") (pintype "passive"))
    )
    (net (code "97") (name "unconnected-(X2-PadB28)") (class "Default")
      (node (ref "X2") (pin "B28") (pinfunction "B28_B28") (pintype "passive"))
    )
    (net (code "98") (name "unconnected-(X2-PadB29)") (class "Default")
      (node (ref "X2") (pin "B29") (pinfunction "B29_B29") (pintype "passive"))
    )
    (net (code "99") (name "unconnected-(X2-PadB30)") (class "Default")
      (node (ref "X2") (pin "B30") (pinfunction "B30_B30") (pintype "passive"))
    )
    (net (code "100") (name "unconnected-(X2-PadB31)") (class "Default")
      (node (ref "X2") (pin "B31") (pinfunction "B31_B31") (pintype "passive"))
    )
    (net (code "101") (name "unconnected-(X3-Pad97)") (class "Default")
      (node (ref "X3") (pin "97") (pinfunction "97_97") (pintype "passive"))
    )
    (net (code "102") (name "unconnected-(X3-Pad98)") (class "Default")
      (node (ref "X3") (pin "98") (pinfunction "98_98") (pintype "passive"))
    )
    (net (code "103") (name "unconnected-(X3-PadA31)") (class "Default")
      (node (ref "X3") (pin "A31") (pinfunction "A31_A31") (pintype "passive"))
    )
    (net (code "104") (name "unconnected-(X3-PadB5)") (class "Default")
      (node (ref "X3") (pin "B5") (pinfunction "B5_B5") (pintype "passive"))
    )
    (net (code "105") (name "unconnected-(X3-PadB6)") (class "Default")
      (node (ref "X3") (pin "B6") (pinfunction "B6_B6") (pintype "passive"))
    )
    (net (code "106") (name "unconnected-(X3-PadB7)") (class "Default")
      (node (ref "X3") (pin "B7") (pinfunction "B7_B7") (pintype "passive"))
    )
    (net (code "107") (name "unconnected-(X3-PadB8)") (class "Default")
      (node (ref "X3") (pin "B8") (pinfunction "B8_B8") (pintype "passive"))
    )
    (net (code "108") (name "unconnected-(X3-PadB9)") (class "Default")
      (node (ref "X3") (pin "B9") (pinfunction "B9_B9") (pintype "passive"))
    )
    (net (code "109") (name "unconnected-(X3-PadB10)") (class "Default")
      (node (ref "X3") (pin "B10") (pinfunction "B10_B10") (pintype "passive"))
    )
    (net (code "110") (name "unconnected-(X3-PadB12)") (class "Default")
      (node (ref "X3") (pin "B12") (pinfunction "B12_B12") (pintype "passive"))
    )
    (net (code "111") (name "unconnected-(X3-PadB13)") (class "Default")
      (node (ref "X3") (pin "B13") (pinfunction "B13_B13") (pintype "passive"))
    )
    (net (code "112") (name "unconnected-(X3-PadB14)") (class "Default")
      (node (ref "X3") (pin "B14") (pinfunction "B14_B14") (pintype "passive"))
    )
    (net (code "113") (name "unconnected-(X3-PadB15)") (class "Default")
      (node (ref "X3") (pin "B15") (pinfunction "B15_B15") (pintype "passive"))
    )
    (net (code "114") (name "unconnected-(X3-PadB16)") (class "Default")
      (node (ref "X3") (pin "B16") (pinfunction "B16_B16") (pintype "passive"))
    )
    (net (code "115") (name "unconnected-(X3-PadB17)") (class "Default")
      (node (ref "X3") (pin "B17") (pinfunction "B17_B17") (pintype "passive"))
    )
    (net (code "116") (name "unconnected-(X3-PadB19)") (class "Default")
      (node (ref "X3") (pin "B19") (pinfunction "B19_B19") (pintype "passive"))
    )
    (net (code "117") (name "unconnected-(X3-PadB20)") (class "Default")
      (node (ref "X3") (pin "B20") (pinfunction "B20_B20") (pintype "passive"))
    )
    (net (code "118") (name "unconnected-(X3-PadB21)") (class "Default")
      (node (ref "X3") (pin "B21") (pinfunction "B21_B21") (pintype "passive"))
    )
    (net (code "119") (name "unconnected-(X3-PadB22)") (class "Default")
      (node (ref "X3") (pin "B22") (pinfunction "B22_B22") (pintype "passive"))
    )
    (net (code "120") (name "unconnected-(X3-PadB23)") (class "Default")
      (node (ref "X3") (pin "B23") (pinfunction "B23_B23") (pintype "passive"))
    )
    (net (code "121") (name "unconnected-(X3-PadB24)") (class "Default")
      (node (ref "X3") (pin "B24") (pinfunction "B24_B24") (pintype "passive"))
    )
    (net (code "122") (name "unconnected-(X3-PadB26)") (class "Default")
      (node (ref "X3") (pin "B26") (pinfunction "B26_B26") (pintype "passive"))
    )
    (net (code "123") (name "unconnected-(X3-PadB27)") (class "Default")
      (node (ref "X3") (pin "B27") (pinfunction "B27_B27") (pintype "passive"))
    )
    (net (code "124") (name "unconnected-(X3-PadB28)") (class "Default")
      (node (ref "X3") (pin "B28") (pinfunction "B28_B28") (pintype "passive"))
    )
    (net (code "125") (name "unconnected-(X3-PadB29)") (class "Default")
      (node (ref "X3") (pin "B29") (pinfunction "B29_B29") (pintype "passive"))
    )
    (net (code "126") (name "unconnected-(X3-PadB30)") (class "Default")
      (node (ref "X3") (pin "B30") (pinfunction "B30_B30") (pintype "passive"))
    )
    (net (code "127") (name "unconnected-(X3-PadB31)") (class "Default")
      (node (ref "X3") (pin "B31") (pinfunction "B31_B31") (pintype "passive"))
    )
    (net (code "128") (name "unconnected-(X4-Pad97)") (class "Default")
      (node (ref "X4") (pin "97") (pinfunction "97_97") (pintype "passive"))
    )
    (net (code "129") (name "unconnected-(X4-Pad98)") (class "Default")
      (node (ref "X4") (pin "98") (pinfunction "98_98") (pintype "passive"))
    )
    (net (code "130") (name "unconnected-(X4-PadA31)") (class "Default")
      (node (ref "X4") (pin "A31") (pinfunction "A31_A31") (pintype "passive"))
    )
    (net (code "131") (name "unconnected-(X4-PadB5)") (class "Default")
      (node (ref "X4") (pin "B5") (pinfunction "B5_B5") (pintype "passive"))
    )
    (net (code "132") (name "unconnected-(X4-PadB6)") (class "Default")
      (node (ref "X4") (pin "B6") (pinfunction "B6_B6") (pintype "passive"))
    )
    (net (code "133") (name "unconnected-(X4-PadB7)") (class "Default")
      (node (ref "X4") (pin "B7") (pinfunction "B7_B7") (pintype "passive"))
    )
    (net (code "134") (name "unconnected-(X4-PadB8)") (class "Default")
      (node (ref "X4") (pin "B8") (pinfunction "B8_B8") (pintype "passive"))
    )
    (net (code "135") (name "unconnected-(X4-PadB9)") (class "Default")
      (node (ref "X4") (pin "B9") (pinfunction "B9_B9") (pintype "passive"))
    )
    (net (code "136") (name "unconnected-(X4-PadB10)") (class "Default")
      (node (ref "X4") (pin "B10") (pinfunction "B10_B10") (pintype "passive"))
    )
    (net (code "137") (name "unconnected-(X4-PadB12)") (class "Default")
      (node (ref "X4") (pin "B12") (pinfunction "B12_B12") (pintype "passive"))
    )
    (net (code "138") (name "unconnected-(X4-PadB13)") (class "Default")
      (node (ref "X4") (pin "B13") (pinfunction "B13_B13") (pintype "passive"))
    )
    (net (code "139") (name "unconnected-(X4-PadB14)") (class "Default")
      (node (ref "X4") (pin "B14") (pinfunction "B14_B14") (pintype "passive"))
    )
    (net (code "140") (name "unconnected-(X4-PadB15)") (class "Default")
      (node (ref "X4") (pin "B15") (pinfunction "B15_B15") (pintype "passive"))
    )
    (net (code "141") (name "unconnected-(X4-PadB16)") (class "Default")
      (node (ref "X4") (pin "B16") (pinfunction "B16_B16") (pintype "passive"))
    )
    (net (code "142") (name "unconnected-(X4-PadB17)") (class "Default")
      (node (ref "X4") (pin "B17") (pinfunction "B17_B17") (pintype "passive"))
    )
    (net (code "143") (name "unconnected-(X4-PadB19)") (class "Default")
      (node (ref "X4") (pin "B19") (pinfunction "B19_B19") (pintype "passive"))
    )
    (net (code "144") (name "unconnected-(X4-PadB20)") (class "Default")
      (node (ref "X4") (pin "B20") (pinfunction "B20_B20") (pintype "passive"))
    )
    (net (code "145") (name "unconnected-(X4-PadB21)") (class "Default")
      (node (ref "X4") (pin "B21") (pinfunction "B21_B21") (pintype "passive"))
    )
    (net (code "146") (name "unconnected-(X4-PadB22)") (class "Default")
      (node (ref "X4") (pin "B22") (pinfunction "B22_B22") (pintype "passive"))
    )
    (net (code "147") (name "unconnected-(X4-PadB23)") (class "Default")
      (node (ref "X4") (pin "B23") (pinfunction "B23_B23") (pintype "passive"))
    )
    (net (code "148") (name "unconnected-(X4-PadB24)") (class "Default")
      (node (ref "X4") (pin "B24") (pinfunction "B24_B24") (pintype "passive"))
    )
    (net (code "149") (name "unconnected-(X4-PadB26)") (class "Default")
      (node (ref "X4") (pin "B26") (pinfunction "B26_B26") (pintype "passive"))
    )
    (net (code "150") (name "unconnected-(X4-PadB27)") (class "Default")
      (node (ref "X4") (pin "B27") (pinfunction "B27_B27") (pintype "passive"))
    )
    (net (code "151") (name "unconnected-(X4-PadB28)") (class "Default")
      (node (ref "X4") (pin "B28") (pinfunction "B28_B28") (pintype "passive"))
    )
    (net (code "152") (name "unconnected-(X4-PadB29)") (class "Default")
      (node (ref "X4") (pin "B29") (pinfunction "B29_B29") (pintype "passive"))
    )
    (net (code "153") (name "unconnected-(X4-PadB30)") (class "Default")
      (node (ref "X4") (pin "B30") (pinfunction "B30_B30") (pintype "passive"))
    )
    (net (code "154") (name "unconnected-(X4-PadB31)") (class "Default")
      (node (ref "X4") (pin "B31") (pinfunction "B31_B31") (pintype "passive"))
    )
    (net (code "155") (name "unconnected-(X5-Pad97)") (class "Default")
      (node (ref "X5") (pin "97") (pinfunction "97_97") (pintype "passive"))
    )
    (net (code "156") (name "unconnected-(X5-Pad98)") (class "Default")
      (node (ref "X5") (pin "98") (pinfunction "98_98") (pintype "passive"))
    )
    (net (code "157") (name "unconnected-(X5-PadA31)") (class "Default")
      (node (ref "X5") (pin "A31") (pinfunction "A31_A31") (pintype "passive"))
    )
    (net (code "158") (name "unconnected-(X5-PadB5)") (class "Default")
      (node (ref "X5") (pin "B5") (pinfunction "B5_B5") (pintype "passive"))
    )
    (net (code "159") (name "unconnected-(X5-PadB6)") (class "Default")
      (node (ref "X5") (pin "B6") (pinfunction "B6_B6") (pintype "passive"))
    )
    (net (code "160") (name "unconnected-(X5-PadB7)") (class "Default")
      (node (ref "X5") (pin "B7") (pinfunction "B7_B7") (pintype "passive"))
    )
    (net (code "161") (name "unconnected-(X5-PadB8)") (class "Default")
      (node (ref "X5") (pin "B8") (pinfunction "B8_B8") (pintype "passive"))
    )
    (net (code "162") (name "unconnected-(X5-PadB9)") (class "Default")
      (node (ref "X5") (pin "B9") (pinfunction "B9_B9") (pintype "passive"))
    )
    (net (code "163") (name "unconnected-(X5-PadB10)") (class "Default")
      (node (ref "X5") (pin "B10") (pinfunction "B10_B10") (pintype "passive"))
    )
    (net (code "164") (name "unconnected-(X5-PadB12)") (class "Default")
      (node (ref "X5") (pin "B12") (pinfunction "B12_B12") (pintype "passive"))
    )
    (net (code "165") (name "unconnected-(X5-PadB13)") (class "Default")
      (node (ref "X5") (pin "B13") (pinfunction "B13_B13") (pintype "passive"))
    )
    (net (code "166") (name "unconnected-(X5-PadB14)") (class "Default")
      (node (ref "X5") (pin "B14") (pinfunction "B14_B14") (pintype "passive"))
    )
    (net (code "167") (name "unconnected-(X5-PadB15)") (class "Default")
      (node (ref "X5") (pin "B15") (pinfunction "B15_B15") (pintype "passive"))
    )
    (net (code "168") (name "unconnected-(X5-PadB16)") (class "Default")
      (node (ref "X5") (pin "B16") (pinfunction "B16_B16") (pintype "passive"))
    )
    (net (code "169") (name "unconnected-(X5-PadB17)") (class "Default")
      (node (ref "X5") (pin "B17") (pinfunction "B17_B17") (pintype "passive"))
    )
    (net (code "170") (name "unconnected-(X5-PadB19)") (class "Default")
      (node (ref "X5") (pin "B19") (pinfunction "B19_B19") (pintype "passive"))
    )
    (net (code "171") (name "unconnected-(X5-PadB20)") (class "Default")
      (node (ref "X5") (pin "B20") (pinfunction "B20_B20") (pintype "passive"))
    )
    (net (code "172") (name "unconnected-(X5-PadB21)") (class "Default")
      (node (ref "X5") (pin "B21") (pinfunction "B21_B21") (pintype "passive"))
    )
    (net (code "173") (name "unconnected-(X5-PadB22)") (class "Default")
      (node (ref "X5") (pin "B22") (pinfunction "B22_B22") (pintype "passive"))
    )
    (net (code "174") (name "unconnected-(X5-PadB23)") (class "Default")
      (node (ref "X5") (pin "B23") (pinfunction "B23_B23") (pintype "passive"))
    )
    (net (code "175") (name "unconnected-(X5-PadB24)") (class "Default")
      (node (ref "X5") (pin "B24") (pinfunction "B24_B24") (pintype "passive"))
    )
    (net (code "176") (name "unconnected-(X5-PadB26)") (class "Default")
      (node (ref "X5") (pin "B26") (pinfunction "B26_B26") (pintype "passive"))
    )
    (net (code "177") (name "unconnected-(X5-PadB27)") (class "Default")
      (node (ref "X5") (pin "B27") (pinfunction "B27_B27") (pintype "passive"))
    )
    (net (code "178") (name "unconnected-(X5-PadB28)") (class "Default")
      (node (ref "X5") (pin "B28") (pinfunction "B28_B28") (pintype "passive"))
    )
    (net (code "179") (name "unconnected-(X5-PadB29)") (class "Default")
      (node (ref "X5") (pin "B29") (pinfunction "B29_B29") (pintype "passive"))
    )
    (net (code "180") (name "unconnected-(X5-PadB30)") (class "Default")
      (node (ref "X5") (pin "B30") (pinfunction "B30_B30") (pintype "passive"))
    )
    (net (code "181") (name "unconnected-(X5-PadB31)") (class "Default")
      (node (ref "X5") (pin "B31") (pinfunction "B31_B31") (pintype "passive"))
    )
    (net (code "182") (name "unconnected-(X6-Pad97)") (class "Default")
      (node (ref "X6") (pin "97") (pinfunction "97_97") (pintype "passive"))
    )
    (net (code "183") (name "unconnected-(X6-Pad98)") (class "Default")
      (node (ref "X6") (pin "98") (pinfunction "98_98") (pintype "passive"))
    )
    (net (code "184") (name "unconnected-(X6-PadA31)") (class "Default")
      (node (ref "X6") (pin "A31") (pinfunction "A31_A31") (pintype "passive"))
    )
    (net (code "185") (name "unconnected-(X6-PadB5)") (class "Default")
      (node (ref "X6") (pin "B5") (pinfunction "B5_B5") (pintype "passive"))
    )
    (net (code "186") (name "unconnected-(X6-PadB6)") (class "Default")
      (node (ref "X6") (pin "B6") (pinfunction "B6_B6") (pintype "passive"))
    )
    (net (code "187") (name "unconnected-(X6-PadB7)") (class "Default")
      (node (ref "X6") (pin "B7") (pinfunction "B7_B7") (pintype "passive"))
    )
    (net (code "188") (name "unconnected-(X6-PadB8)") (class "Default")
      (node (ref "X6") (pin "B8") (pinfunction "B8_B8") (pintype "passive"))
    )
    (net (code "189") (name "unconnected-(X6-PadB9)") (class "Default")
      (node (ref "X6") (pin "B9") (pinfunction "B9_B9") (pintype "passive"))
    )
    (net (code "190") (name "unconnected-(X6-PadB10)") (class "Default")
      (node (ref "X6") (pin "B10") (pinfunction "B10_B10") (pintype "passive"))
    )
    (net (code "191") (name "unconnected-(X6-PadB12)") (class "Default")
      (node (ref "X6") (pin "B12") (pinfunction "B12_B12") (pintype "passive"))
    )
    (net (code "192") (name "unconnected-(X6-PadB13)") (class "Default")
      (node (ref "X6") (pin "B13") (pinfunction "B13_B13") (pintype "passive"))
    )
    (net (code "193") (name "unconnected-(X6-PadB14)") (class "Default")
      (node (ref "X6") (pin "B14") (pinfunction "B14_B14") (pintype "passive"))
    )
    (net (code "194") (name "unconnected-(X6-PadB15)") (class "Default")
      (node (ref "X6") (pin "B15") (pinfunction "B15_B15") (pintype "passive"))
    )
    (net (code "195") (name "unconnected-(X6-PadB16)") (class "Default")
      (node (ref "X6") (pin "B16") (pinfunction "B16_B16") (pintype "passive"))
    )
    (net (code "196") (name "unconnected-(X6-PadB17)") (class "Default")
      (node (ref "X6") (pin "B17") (pinfunction "B17_B17") (pintype "passive"))
    )
    (net (code "197") (name "unconnected-(X6-PadB19)") (class "Default")
      (node (ref "X6") (pin "B19") (pinfunction "B19_B19") (pintype "passive"))
    )
    (net (code "198") (name "unconnected-(X6-PadB20)") (class "Default")
      (node (ref "X6") (pin "B20") (pinfunction "B20_B20") (pintype "passive"))
    )
    (net (code "199") (name "unconnected-(X6-PadB21)") (class "Default")
      (node (ref "X6") (pin "B21") (pinfunction "B21_B21") (pintype "passive"))
    )
    (net (code "200") (name "unconnected-(X6-PadB22)") (class "Default")
      (node (ref "X6") (pin "B22") (pinfunction "B22_B22") (pintype "passive"))
    )
    (net (code "201") (name "unconnected-(X6-PadB23)") (class "Default")
      (node (ref "X6") (pin "B23") (pinfunction "B23_B23") (pintype "passive"))
    )
    (net (code "202") (name "unconnected-(X6-PadB24)") (class "Default")
      (node (ref "X6") (pin "B24") (pinfunction "B24_B24") (pintype "passive"))
    )
    (net (code "203") (name "unconnected-(X6-PadB26)") (class "Default")
      (node (ref "X6") (pin "B26") (pinfunction "B26_B26") (pintype "passive"))
    )
    (net (code "204") (name "unconnected-(X6-PadB27)") (class "Default")
      (node (ref "X6") (pin "B27") (pinfunction "B27_B27") (pintype "passive"))
    )
    (net (code "205") (name "unconnected-(X6-PadB28)") (class "Default")
      (node (ref "X6") (pin "B28") (pinfunction "B28_B28") (pintype "passive"))
    )
    (net (code "206") (name "unconnected-(X6-PadB29)") (class "Default")
      (node (ref "X6") (pin "B29") (pinfunction "B29_B29") (pintype "passive"))
    )
    (net (code "207") (name "unconnected-(X6-PadB30)") (class "Default")
      (node (ref "X6") (pin "B30") (pinfunction "B30_B30") (pintype "passive"))
    )
    (net (code "208") (name "unconnected-(X6-PadB31)") (class "Default")
      (node (ref "X6") (pin "B31") (pinfunction "B31_B31") (pintype "passive"))
    )
    (net (code "209") (name "unconnected-(X7-Pad97)") (class "Default")
      (node (ref "X7") (pin "97") (pinfunction "97_97") (pintype "passive"))
    )
    (net (code "210") (name "unconnected-(X7-Pad98)") (class "Default")
      (node (ref "X7") (pin "98") (pinfunction "98_98") (pintype "passive"))
    )
    (net (code "211") (name "unconnected-(X7-PadB5)") (class "Default")
      (node (ref "X7") (pin "B5") (pinfunction "B5_B5") (pintype "passive"))
    )
    (net (code "212") (name "unconnected-(X7-PadB6)") (class "Default")
      (node (ref "X7") (pin "B6") (pinfunction "B6_B6") (pintype "passive"))
    )
    (net (code "213") (name "unconnected-(X7-PadB7)") (class "Default")
      (node (ref "X7") (pin "B7") (pinfunction "B7_B7") (pintype "passive"))
    )
    (net (code "214") (name "unconnected-(X7-PadB8)") (class "Default")
      (node (ref "X7") (pin "B8") (pinfunction "B8_B8") (pintype "passive"))
    )
    (net (code "215") (name "unconnected-(X7-PadB9)") (class "Default")
      (node (ref "X7") (pin "B9") (pinfunction "B9_B9") (pintype "passive"))
    )
    (net (code "216") (name "unconnected-(X7-PadB10)") (class "Default")
      (node (ref "X7") (pin "B10") (pinfunction "B10_B10") (pintype "passive"))
    )
    (net (code "217") (name "unconnected-(X7-PadB12)") (class "Default")
      (node (ref "X7") (pin "B12") (pinfunction "B12_B12") (pintype "passive"))
    )
    (net (code "218") (name "unconnected-(X7-PadB13)") (class "Default")
      (node (ref "X7") (pin "B13") (pinfunction "B13_B13") (pintype "passive"))
    )
    (net (code "219") (name "unconnected-(X7-PadB14)") (class "Default")
      (node (ref "X7") (pin "B14") (pinfunction "B14_B14") (pintype "passive"))
    )
    (net (code "220") (name "unconnected-(X7-PadB15)") (class "Default")
      (node (ref "X7") (pin "B15") (pinfunction "B15_B15") (pintype "passive"))
    )
    (net (code "221") (name "unconnected-(X7-PadB16)") (class "Default")
      (node (ref "X7") (pin "B16") (pinfunction "B16_B16") (pintype "passive"))
    )
    (net (code "222") (name "unconnected-(X7-PadB17)") (class "Default")
      (node (ref "X7") (pin "B17") (pinfunction "B17_B17") (pintype "passive"))
    )
    (net (code "223") (name "unconnected-(X7-PadB19)") (class "Default")
      (node (ref "X7") (pin "B19") (pinfunction "B19_B19") (pintype "passive"))
    )
    (net (code "224") (name "unconnected-(X7-PadB20)") (class "Default")
      (node (ref "X7") (pin "B20") (pinfunction "B20_B20") (pintype "passive"))
    )
    (net (code "225") (name "unconnected-(X7-PadB21)") (class "Default")
      (node (ref "X7") (pin "B21") (pinfunction "B21_B21") (pintype "passive"))
    )
    (net (code "226") (name "unconnected-(X7-PadB22)") (class "Default")
      (node (ref "X7") (pin "B22") (pinfunction "B22_B22") (pintype "passive"))
    )
    (net (code "227") (name "unconnected-(X7-PadB23)") (class "Default")
      (node (ref "X7") (pin "B23") (pinfunction "B23_B23") (pintype "passive"))
    )
    (net (code "228") (name "unconnected-(X7-PadB24)") (class "Default")
      (node (ref "X7") (pin "B24") (pinfunction "B24_B24") (pintype "passive"))
    )
    (net (code "229") (name "unconnected-(X7-PadB26)") (class "Default")
      (node (ref "X7") (pin "B26") (pinfunction "B26_B26") (pintype "passive"))
    )
    (net (code "230") (name "unconnected-(X7-PadB27)") (class "Default")
      (node (ref "X7") (pin "B27") (pinfunction "B27_B27") (pintype "passive"))
    )
    (net (code "231") (name "unconnected-(X7-PadB28)") (class "Default")
      (node (ref "X7") (pin "B28") (pinfunction "B28_B28") (pintype "passive"))
    )
    (net (code "232") (name "unconnected-(X7-PadB29)") (class "Default")
      (node (ref "X7") (pin "B29") (pinfunction "B29_B29") (pintype "passive"))
    )
    (net (code "233") (name "unconnected-(X8-Pad97)") (class "Default")
      (node (ref "X8") (pin "97") (pinfunction "97_97") (pintype "passive"))
    )
    (net (code "234") (name "unconnected-(X8-Pad98)") (class "Default")
      (node (ref "X8") (pin "98") (pinfunction "98_98") (pintype "passive"))
    )
    (net (code "235") (name "unconnected-(X8-PadB5)") (class "Default")
      (node (ref "X8") (pin "B5") (pinfunction "B5_B5") (pintype "passive"))
    )
    (net (code "236") (name "unconnected-(X8-PadB6)") (class "Default")
      (node (ref "X8") (pin "B6") (pinfunction "B6_B6") (pintype "passive"))
    )
    (net (code "237") (name "unconnected-(X8-PadB7)") (class "Default")
      (node (ref "X8") (pin "B7") (pinfunction "B7_B7") (pintype "passive"))
    )
    (net (code "238") (name "unconnected-(X8-PadB8)") (class "Default")
      (node (ref "X8") (pin "B8") (pinfunction "B8_B8") (pintype "passive"))
    )
    (net (code "239") (name "unconnected-(X8-PadB9)") (class "Default")
      (node (ref "X8") (pin "B9") (pinfunction "B9_B9") (pintype "passive"))
    )
    (net (code "240") (name "unconnected-(X8-PadB10)") (class "Default")
      (node (ref "X8") (pin "B10") (pinfunction "B10_B10") (pintype "passive"))
    )
    (net (code "241") (name "unconnected-(X8-PadB12)") (class "Default")
      (node (ref "X8") (pin "B12") (pinfunction "B12_B12") (pintype "passive"))
    )
    (net (code "242") (name "unconnected-(X8-PadB13)") (class "Default")
      (node (ref "X8") (pin "B13") (pinfunction "B13_B13") (pintype "passive"))
    )
    (net (code "243") (name "unconnected-(X8-PadB14)") (class "Default")
      (node (ref "X8") (pin "B14") (pinfunction "B14_B14") (pintype "passive"))
    )
    (net (code "244") (name "unconnected-(X8-PadB15)") (class "Default")
      (node (ref "X8") (pin "B15") (pinfunction "B15_B15") (pintype "passive"))
    )
    (net (code "245") (name "unconnected-(X8-PadB16)") (class "Default")
      (node (ref "X8") (pin "B16") (pinfunction "B16_B16") (pintype "passive"))
    )
    (net (code "246") (name "unconnected-(X8-PadB17)") (class "Default")
      (node (ref "X8") (pin "B17") (pinfunction "B17_B17") (pintype "passive"))
    )
    (net (code "247") (name "unconnected-(X8-PadB19)") (class "Default")
      (node (ref "X8") (pin "B19") (pinfunction "B19_B19") (pintype "passive"))
    )
    (net (code "248") (name "unconnected-(X8-PadB20)") (class "Default")
      (node (ref "X8") (pin "B20") (pinfunction "B20_B20") (pintype "passive"))
    )
    (net (code "249") (name "unconnected-(X8-PadB21)") (class "Default")
      (node (ref "X8") (pin "B21") (pinfunction "B21_B21") (pintype "passive"))
    )
    (net (code "250") (name "unconnected-(X8-PadB22)") (class "Default")
      (node (ref "X8") (pin "B22") (pinfunction "B22_B22") (pintype "passive"))
    )
    (net (code "251") (name "unconnected-(X8-PadB23)") (class "Default")
      (node (ref "X8") (pin "B23") (pinfunction "B23_B23") (pintype "passive"))
    )
    (net (code "252") (name "unconnected-(X8-PadB24)") (class "Default")
      (node (ref "X8") (pin "B24") (pinfunction "B24_B24") (pintype "passive"))
    )
    (net (code "253") (name "unconnected-(X8-PadB26)") (class "Default")
      (node (ref "X8") (pin "B26") (pinfunction "B26_B26") (pintype "passive"))
    )
    (net (code "254") (name "unconnected-(X8-PadB27)") (class "Default")
      (node (ref "X8") (pin "B27") (pinfunction "B27_B27") (pintype "passive"))
    )
    (net (code "255") (name "unconnected-(X8-PadB28)") (class "Default")
      (node (ref "X8") (pin "B28") (pinfunction "B28_B28") (pintype "passive"))
    )
    (net (code "256") (name "unconnected-(X8-PadB29)") (class "Default")
      (node (ref "X8") (pin "B29") (pinfunction "B29_B29") (pintype "passive"))
    )
    (net (code "257") (name "unconnected-(X9-Pad97)") (class "Default")
      (node (ref "X9") (pin "97") (pinfunction "97_97") (pintype "passive"))
    )
    (net (code "258") (name "unconnected-(X9-Pad98)") (class "Default")
      (node (ref "X9") (pin "98") (pinfunction "98_98") (pintype "passive"))
    )
    (net (code "259") (name "unconnected-(X9-PadA31)") (class "Default")
      (node (ref "X9") (pin "A31") (pinfunction "A31_A31") (pintype "passive"))
    )
    (net (code "260") (name "unconnected-(X9-PadB5)") (class "Default")
      (node (ref "X9") (pin "B5") (pinfunction "B5_B5") (pintype "passive"))
    )
    (net (code "261") (name "unconnected-(X9-PadB6)") (class "Default")
      (node (ref "X9") (pin "B6") (pinfunction "B6_B6") (pintype "passive"))
    )
    (net (code "262") (name "unconnected-(X9-PadB7)") (class "Default")
      (node (ref "X9") (pin "B7") (pinfunction "B7_B7") (pintype "passive"))
    )
    (net (code "263") (name "unconnected-(X9-PadB8)") (class "Default")
      (node (ref "X9") (pin "B8") (pinfunction "B8_B8") (pintype "passive"))
    )
    (net (code "264") (name "unconnected-(X9-PadB9)") (class "Default")
      (node (ref "X9") (pin "B9") (pinfunction "B9_B9") (pintype "passive"))
    )
    (net (code "265") (name "unconnected-(X9-PadB10)") (class "Default")
      (node (ref "X9") (pin "B10") (pinfunction "B10_B10") (pintype "passive"))
    )
    (net (code "266") (name "unconnected-(X9-PadB12)") (class "Default")
      (node (ref "X9") (pin "B12") (pinfunction "B12_B12") (pintype "passive"))
    )
    (net (code "267") (name "unconnected-(X9-PadB13)") (class "Default")
      (node (ref "X9") (pin "B13") (pinfunction "B13_B13") (pintype "passive"))
    )
    (net (code "268") (name "unconnected-(X9-PadB14)") (class "Default")
      (node (ref "X9") (pin "B14") (pinfunction "B14_B14") (pintype "passive"))
    )
    (net (code "269") (name "unconnected-(X9-PadB15)") (class "Default")
      (node (ref "X9") (pin "B15") (pinfunction "B15_B15") (pintype "passive"))
    )
    (net (code "270") (name "unconnected-(X9-PadB16)") (class "Default")
      (node (ref "X9") (pin "B16") (pinfunction "B16_B16") (pintype "passive"))
    )
    (net (code "271") (name "unconnected-(X9-PadB17)") (class "Default")
      (node (ref "X9") (pin "B17") (pinfunction "B17_B17") (pintype "passive"))
    )
    (net (code "272") (name "unconnected-(X9-PadB19)") (class "Default")
      (node (ref "X9") (pin "B19") (pinfunction "B19_B19") (pintype "passive"))
    )
    (net (code "273") (name "unconnected-(X9-PadB20)") (class "Default")
      (node (ref "X9") (pin "B20") (pinfunction "B20_B20") (pintype "passive"))
    )
    (net (code "274") (name "unconnected-(X9-PadB21)") (class "Default")
      (node (ref "X9") (pin "B21") (pinfunction "B21_B21") (pintype "passive"))
    )
    (net (code "275") (name "unconnected-(X9-PadB22)") (class "Default")
      (node (ref "X9") (pin "B22") (pinfunction "B22_B22") (pintype "passive"))
    )
    (net (code "276") (name "unconnected-(X9-PadB23)") (class "Default")
      (node (ref "X9") (pin "B23") (pinfunction "B23_B23") (pintype "passive"))
    )
    (net (code "277") (name "unconnected-(X9-PadB24)") (class "Default")
      (node (ref "X9") (pin "B24") (pinfunction "B24_B24") (pintype "passive"))
    )
    (net (code "278") (name "unconnected-(X9-PadB26)") (class "Default")
      (node (ref "X9") (pin "B26") (pinfunction "B26_B26") (pintype "passive"))
    )
    (net (code "279") (name "unconnected-(X9-PadB27)") (class "Default")
      (node (ref "X9") (pin "B27") (pinfunction "B27_B27") (pintype "passive"))
    )
    (net (code "280") (name "unconnected-(X9-PadB28)") (class "Default")
      (node (ref "X9") (pin "B28") (pinfunction "B28_B28") (pintype "passive"))
    )
    (net (code "281") (name "unconnected-(X9-PadB29)") (class "Default")
      (node (ref "X9") (pin "B29") (pinfunction "B29_B29") (pintype "passive"))
    )
    (net (code "282") (name "unconnected-(X9-PadB30)") (class "Default")
      (node (ref "X9") (pin "B30") (pinfunction "B30_B30") (pintype "passive"))
    )
    (net (code "283") (name "unconnected-(X9-PadB31)") (class "Default")
      (node (ref "X9") (pin "B31") (pinfunction "B31_B31") (pintype "passive"))
    )
    (net (code "284") (name "unconnected-(X10-Pad97)") (class "Default")
      (node (ref "X10") (pin "97") (pinfunction "97_97") (pintype "passive"))
    )
    (net (code "285") (name "unconnected-(X10-Pad98)") (class "Default")
      (node (ref "X10") (pin "98") (pinfunction "98_98") (pintype "passive"))
    )
    (net (code "286") (name "unconnected-(X10-PadA31)") (class "Default")
      (node (ref "X10") (pin "A31") (pinfunction "A31_A31") (pintype "passive"))
    )
    (net (code "287") (name "unconnected-(X10-PadB5)") (class "Default")
      (node (ref "X10") (pin "B5") (pinfunction "B5_B5") (pintype "passive"))
    )
    (net (code "288") (name "unconnected-(X10-PadB6)") (class "Default")
      (node (ref "X10") (pin "B6") (pinfunction "B6_B6") (pintype "passive"))
    )
    (net (code "289") (name "unconnected-(X10-PadB7)") (class "Default")
      (node (ref "X10") (pin "B7") (pinfunction "B7_B7") (pintype "passive"))
    )
    (net (code "290") (name "unconnected-(X10-PadB8)") (class "Default")
      (node (ref "X10") (pin "B8") (pinfunction "B8_B8") (pintype "passive"))
    )
    (net (code "291") (name "unconnected-(X10-PadB9)") (class "Default")
      (node (ref "X10") (pin "B9") (pinfunction "B9_B9") (pintype "passive"))
    )
    (net (code "292") (name "unconnected-(X10-PadB10)") (class "Default")
      (node (ref "X10") (pin "B10") (pinfunction "B10_B10") (pintype "passive"))
    )
    (net (code "293") (name "unconnected-(X10-PadB12)") (class "Default")
      (node (ref "X10") (pin "B12") (pinfunction "B12_B12") (pintype "passive"))
    )
    (net (code "294") (name "unconnected-(X10-PadB13)") (class "Default")
      (node (ref "X10") (pin "B13") (pinfunction "B13_B13") (pintype "passive"))
    )
    (net (code "295") (name "unconnected-(X10-PadB14)") (class "Default")
      (node (ref "X10") (pin "B14") (pinfunction "B14_B14") (pintype "passive"))
    )
    (net (code "296") (name "unconnected-(X10-PadB15)") (class "Default")
      (node (ref "X10") (pin "B15") (pinfunction "B15_B15") (pintype "passive"))
    )
    (net (code "297") (name "unconnected-(X10-PadB16)") (class "Default")
      (node (ref "X10") (pin "B16") (pinfunction "B16_B16") (pintype "passive"))
    )
    (net (code "298") (name "unconnected-(X10-PadB17)") (class "Default")
      (node (ref "X10") (pin "B17") (pinfunction "B17_B17") (pintype "passive"))
    )
    (net (code "299") (name "unconnected-(X10-PadB19)") (class "Default")
      (node (ref "X10") (pin "B19") (pinfunction "B19_B19") (pintype "passive"))
    )
    (net (code "300") (name "unconnected-(X10-PadB20)") (class "Default")
      (node (ref "X10") (pin "B20") (pinfunction "B20_B20") (pintype "passive"))
    )
    (net (code "301") (name "unconnected-(X10-PadB21)") (class "Default")
      (node (ref "X10") (pin "B21") (pinfunction "B21_B21") (pintype "passive"))
    )
    (net (code "302") (name "unconnected-(X10-PadB22)") (class "Default")
      (node (ref "X10") (pin "B22") (pinfunction "B22_B22") (pintype "passive"))
    )
    (net (code "303") (name "unconnected-(X10-PadB23)") (class "Default")
      (node (ref "X10") (pin "B23") (pinfunction "B23_B23") (pintype "passive"))
    )
    (net (code "304") (name "unconnected-(X10-PadB24)") (class "Default")
      (node (ref "X10") (pin "B24") (pinfunction "B24_B24") (pintype "passive"))
    )
    (net (code "305") (name "unconnected-(X10-PadB26)") (class "Default")
      (node (ref "X10") (pin "B26") (pinfunction "B26_B26") (pintype "passive"))
    )
    (net (code "306") (name "unconnected-(X10-PadB27)") (class "Default")
      (node (ref "X10") (pin "B27") (pinfunction "B27_B27") (pintype "passive"))
    )
    (net (code "307") (name "unconnected-(X10-PadB28)") (class "Default")
      (node (ref "X10") (pin "B28") (pinfunction "B28_B28") (pintype "passive"))
    )
    (net (code "308") (name "unconnected-(X10-PadB29)") (class "Default")
      (node (ref "X10") (pin "B29") (pinfunction "B29_B29") (pintype "passive"))
    )
    (net (code "309") (name "unconnected-(X10-PadB30)") (class "Default")
      (node (ref "X10") (pin "B30") (pinfunction "B30_B30") (pintype "passive"))
    )
    (net (code "310") (name "unconnected-(X10-PadB31)") (class "Default")
      (node (ref "X10") (pin "B31") (pinfunction "B31_B31") (pintype "passive"))
    )
    (net (code "311") (name "unconnected-(X11-Pad97)") (class "Default")
      (node (ref "X11") (pin "97") (pinfunction "97_97") (pintype "passive"))
    )
    (net (code "312") (name "unconnected-(X11-Pad98)") (class "Default")
      (node (ref "X11") (pin "98") (pinfunction "98_98") (pintype "passive"))
    )
    (net (code "313") (name "unconnected-(X11-PadA31)") (class "Default")
      (node (ref "X11") (pin "A31") (pinfunction "A31_A31") (pintype "passive"))
    )
    (net (code "314") (name "unconnected-(X11-PadB5)") (class "Default")
      (node (ref "X11") (pin "B5") (pinfunction "B5_B5") (pintype "passive"))
    )
    (net (code "315") (name "unconnected-(X11-PadB6)") (class "Default")
      (node (ref "X11") (pin "B6") (pinfunction "B6_B6") (pintype "passive"))
    )
    (net (code "316") (name "unconnected-(X11-PadB7)") (class "Default")
      (node (ref "X11") (pin "B7") (pinfunction "B7_B7") (pintype "passive"))
    )
    (net (code "317") (name "unconnected-(X11-PadB8)") (class "Default")
      (node (ref "X11") (pin "B8") (pinfunction "B8_B8") (pintype "passive"))
    )
    (net (code "318") (name "unconnected-(X11-PadB9)") (class "Default")
      (node (ref "X11") (pin "B9") (pinfunction "B9_B9") (pintype "passive"))
    )
    (net (code "319") (name "unconnected-(X11-PadB10)") (class "Default")
      (node (ref "X11") (pin "B10") (pinfunction "B10_B10") (pintype "passive"))
    )
    (net (code "320") (name "unconnected-(X11-PadB12)") (class "Default")
      (node (ref "X11") (pin "B12") (pinfunction "B12_B12") (pintype "passive"))
    )
    (net (code "321") (name "unconnected-(X11-PadB13)") (class "Default")
      (node (ref "X11") (pin "B13") (pinfunction "B13_B13") (pintype "passive"))
    )
    (net (code "322") (name "unconnected-(X11-PadB14)") (class "Default")
      (node (ref "X11") (pin "B14") (pinfunction "B14_B14") (pintype "passive"))
    )
    (net (code "323") (name "unconnected-(X11-PadB15)") (class "Default")
      (node (ref "X11") (pin "B15") (pinfunction "B15_B15") (pintype "passive"))
    )
    (net (code "324") (name "unconnected-(X11-PadB16)") (class "Default")
      (node (ref "X11") (pin "B16") (pinfunction "B16_B16") (pintype "passive"))
    )
    (net (code "325") (name "unconnected-(X11-PadB17)") (class "Default")
      (node (ref "X11") (pin "B17") (pinfunction "B17_B17") (pintype "passive"))
    )
    (net (code "326") (name "unconnected-(X11-PadB19)") (class "Default")
      (node (ref "X11") (pin "B19") (pinfunction "B19_B19") (pintype "passive"))
    )
    (net (code "327") (name "unconnected-(X11-PadB20)") (class "Default")
      (node (ref "X11") (pin "B20") (pinfunction "B20_B20") (pintype "passive"))
    )
    (net (code "328") (name "unconnected-(X11-PadB21)") (class "Default")
      (node (ref "X11") (pin "B21") (pinfunction "B21_B21") (pintype "passive"))
    )
    (net (code "329") (name "unconnected-(X11-PadB22)") (class "Default")
      (node (ref "X11") (pin "B22") (pinfunction "B22_B22") (pintype "passive"))
    )
    (net (code "330") (name "unconnected-(X11-PadB23)") (class "Default")
      (node (ref "X11") (pin "B23") (pinfunction "B23_B23") (pintype "passive"))
    )
    (net (code "331") (name "unconnected-(X11-PadB24)") (class "Default")
      (node (ref "X11") (pin "B24") (pinfunction "B24_B24") (pintype "passive"))
    )
    (net (code "332") (name "unconnected-(X11-PadB26)") (class "Default")
      (node (ref "X11") (pin "B26") (pinfunction "B26_B26") (pintype "passive"))
    )
    (net (code "333") (name "unconnected-(X11-PadB27)") (class "Default")
      (node (ref "X11") (pin "B27") (pinfunction "B27_B27") (pintype "passive"))
    )
    (net (code "334") (name "unconnected-(X11-PadB28)") (class "Default")
      (node (ref "X11") (pin "B28") (pinfunction "B28_B28") (pintype "passive"))
    )
    (net (code "335") (name "unconnected-(X11-PadB29)") (class "Default")
      (node (ref "X11") (pin "B29") (pinfunction "B29_B29") (pintype "passive"))
    )
    (net (code "336") (name "unconnected-(X11-PadB30)") (class "Default")
      (node (ref "X11") (pin "B30") (pinfunction "B30_B30") (pintype "passive"))
    )
    (net (code "337") (name "unconnected-(X11-PadB31)") (class "Default")
      (node (ref "X11") (pin "B31") (pinfunction "B31_B31") (pintype "passive"))
    )
    (net (code "338") (name "unconnected-(X12-Pad97)") (class "Default")
      (node (ref "X12") (pin "97") (pinfunction "97_97") (pintype "passive"))
    )
    (net (code "339") (name "unconnected-(X12-Pad98)") (class "Default")
      (node (ref "X12") (pin "98") (pinfunction "98_98") (pintype "passive"))
    )
    (net (code "340") (name "unconnected-(X12-PadA31)") (class "Default")
      (node (ref "X12") (pin "A31") (pinfunction "A31_A31") (pintype "passive"))
    )
    (net (code "341") (name "unconnected-(X12-PadB5)") (class "Default")
      (node (ref "X12") (pin "B5") (pinfunction "B5_B5") (pintype "passive"))
    )
    (net (code "342") (name "unconnected-(X12-PadB6)") (class "Default")
      (node (ref "X12") (pin "B6") (pinfunction "B6_B6") (pintype "passive"))
    )
    (net (code "343") (name "unconnected-(X12-PadB7)") (class "Default")
      (node (ref "X12") (pin "B7") (pinfunction "B7_B7") (pintype "passive"))
    )
    (net (code "344") (name "unconnected-(X12-PadB8)") (class "Default")
      (node (ref "X12") (pin "B8") (pinfunction "B8_B8") (pintype "passive"))
    )
    (net (code "345") (name "unconnected-(X12-PadB9)") (class "Default")
      (node (ref "X12") (pin "B9") (pinfunction "B9_B9") (pintype "passive"))
    )
    (net (code "346") (name "unconnected-(X12-PadB10)") (class "Default")
      (node (ref "X12") (pin "B10") (pinfunction "B10_B10") (pintype "passive"))
    )
    (net (code "347") (name "unconnected-(X12-PadB12)") (class "Default")
      (node (ref "X12") (pin "B12") (pinfunction "B12_B12") (pintype "passive"))
    )
    (net (code "348") (name "unconnected-(X12-PadB13)") (class "Default")
      (node (ref "X12") (pin "B13") (pinfunction "B13_B13") (pintype "passive"))
    )
    (net (code "349") (name "unconnected-(X12-PadB14)") (class "Default")
      (node (ref "X12") (pin "B14") (pinfunction "B14_B14") (pintype "passive"))
    )
    (net (code "350") (name "unconnected-(X12-PadB15)") (class "Default")
      (node (ref "X12") (pin "B15") (pinfunction "B15_B15") (pintype "passive"))
    )
    (net (code "351") (name "unconnected-(X12-PadB16)") (class "Default")
      (node (ref "X12") (pin "B16") (pinfunction "B16_B16") (pintype "passive"))
    )
    (net (code "352") (name "unconnected-(X12-PadB17)") (class "Default")
      (node (ref "X12") (pin "B17") (pinfunction "B17_B17") (pintype "passive"))
    )
    (net (code "353") (name "unconnected-(X12-PadB19)") (class "Default")
      (node (ref "X12") (pin "B19") (pinfunction "B19_B19") (pintype "passive"))
    )
    (net (code "354") (name "unconnected-(X12-PadB20)") (class "Default")
      (node (ref "X12") (pin "B20") (pinfunction "B20_B20") (pintype "passive"))
    )
    (net (code "355") (name "unconnected-(X12-PadB21)") (class "Default")
      (node (ref "X12") (pin "B21") (pinfunction "B21_B21") (pintype "passive"))
    )
    (net (code "356") (name "unconnected-(X12-PadB22)") (class "Default")
      (node (ref "X12") (pin "B22") (pinfunction "B22_B22") (pintype "passive"))
    )
    (net (code "357") (name "unconnected-(X12-PadB23)") (class "Default")
      (node (ref "X12") (pin "B23") (pinfunction "B23_B23") (pintype "passive"))
    )
    (net (code "358") (name "unconnected-(X12-PadB24)") (class "Default")
      (node (ref "X12") (pin "B24") (pinfunction "B24_B24") (pintype "passive"))
    )
    (net (code "359") (name "unconnected-(X12-PadB26)") (class "Default")
      (node (ref "X12") (pin "B26") (pinfunction "B26_B26") (pintype "passive"))
    )
    (net (code "360") (name "unconnected-(X12-PadB27)") (class "Default")
      (node (ref "X12") (pin "B27") (pinfunction "B27_B27") (pintype "passive"))
    )
    (net (code "361") (name "unconnected-(X12-PadB28)") (class "Default")
      (node (ref "X12") (pin "B28") (pinfunction "B28_B28") (pintype "passive"))
    )
    (net (code "362") (name "unconnected-(X12-PadB29)") (class "Default")
      (node (ref "X12") (pin "B29") (pinfunction "B29_B29") (pintype "passive"))
    )
    (net (code "363") (name "unconnected-(X12-PadB30)") (class "Default")
      (node (ref "X12") (pin "B30") (pinfunction "B30_B30") (pintype "passive"))
    )
    (net (code "364") (name "unconnected-(X12-PadB31)") (class "Default")
      (node (ref "X12") (pin "B31") (pinfunction "B31_B31") (pintype "passive"))
    )
  )
)
